# BikeBikeAja_V2.net
KiCad netlist of a schematic drawn in EAGLE
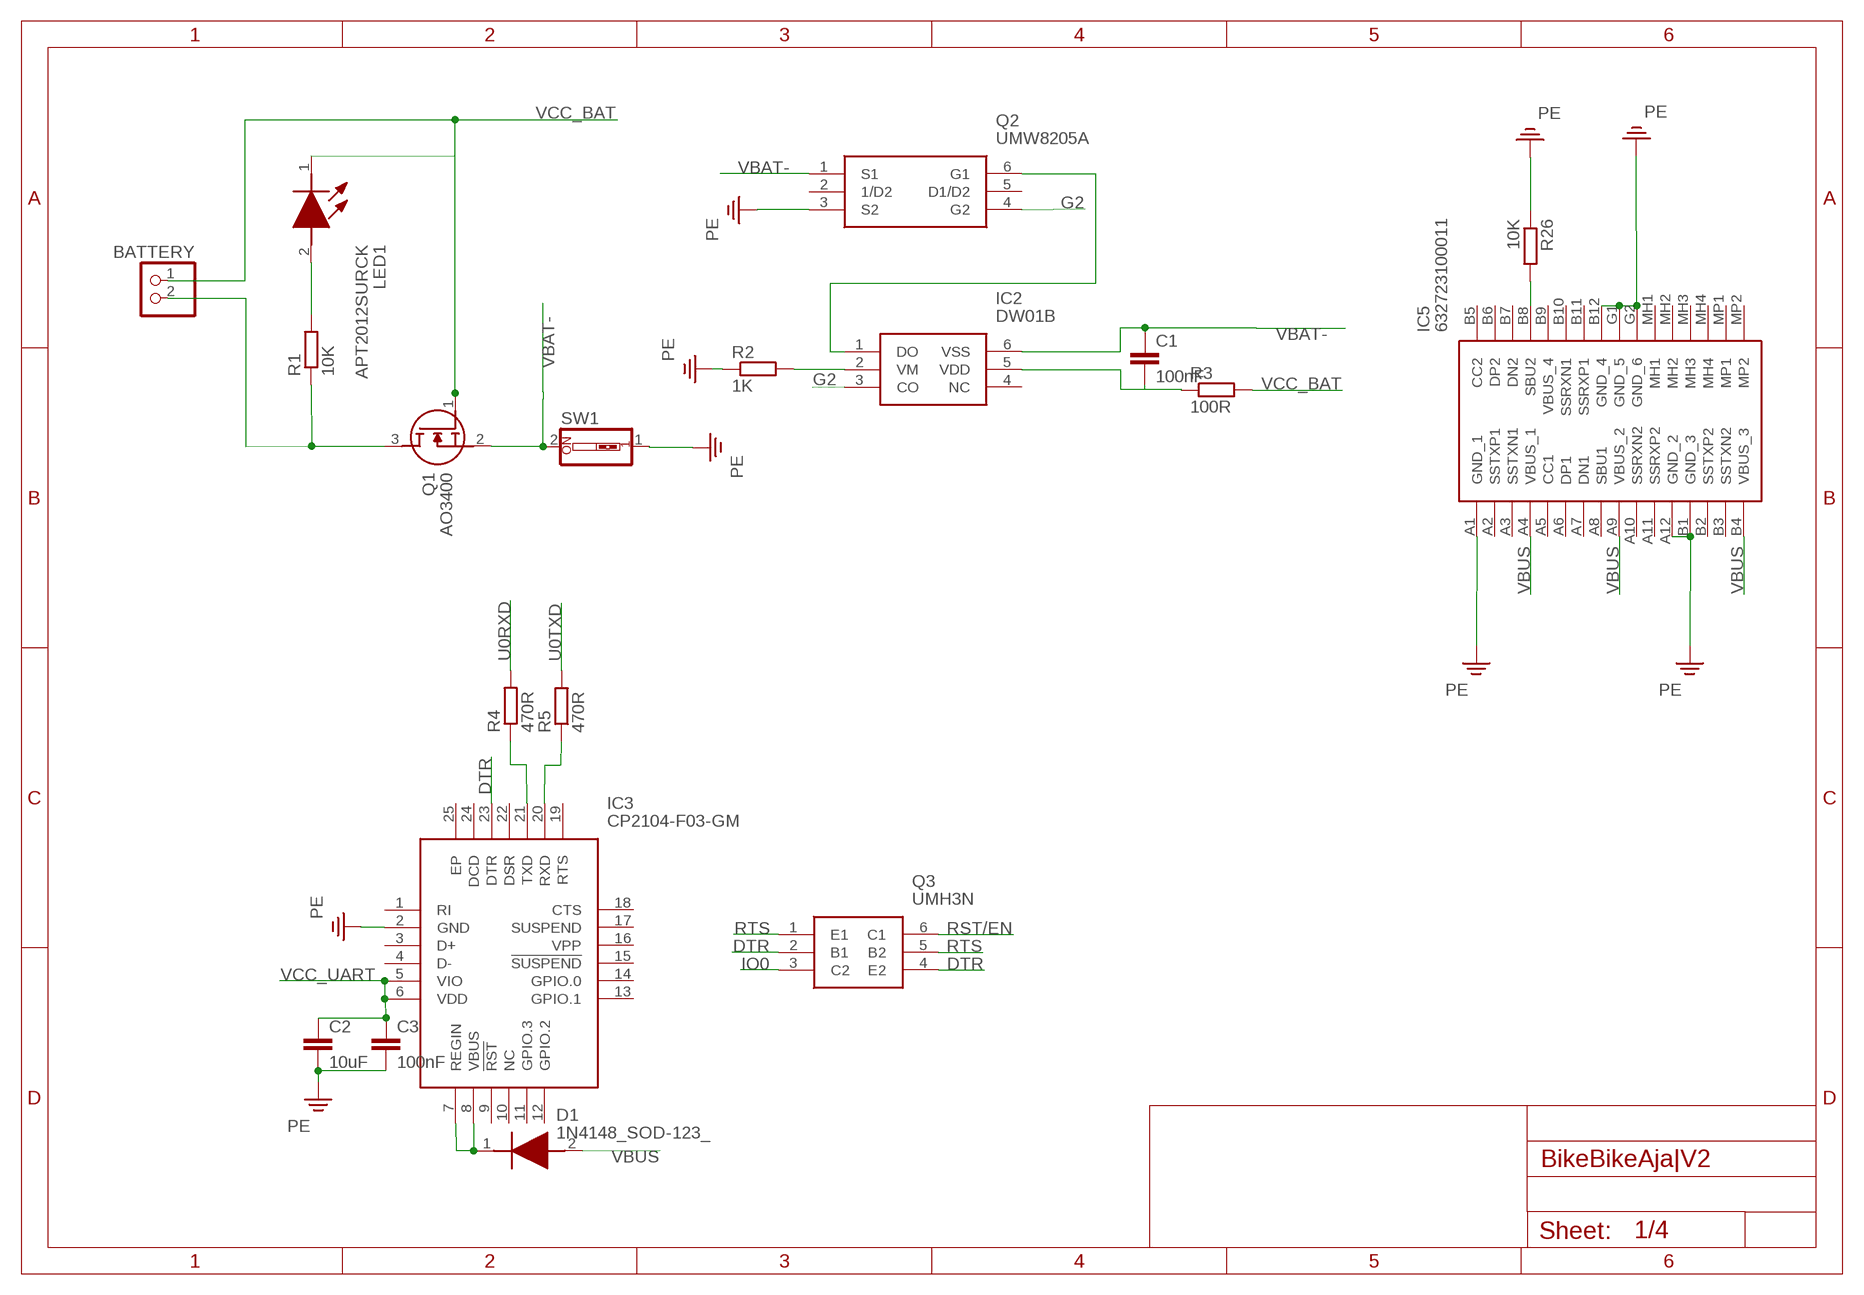
[diagram p0: schematic, sheet 1]
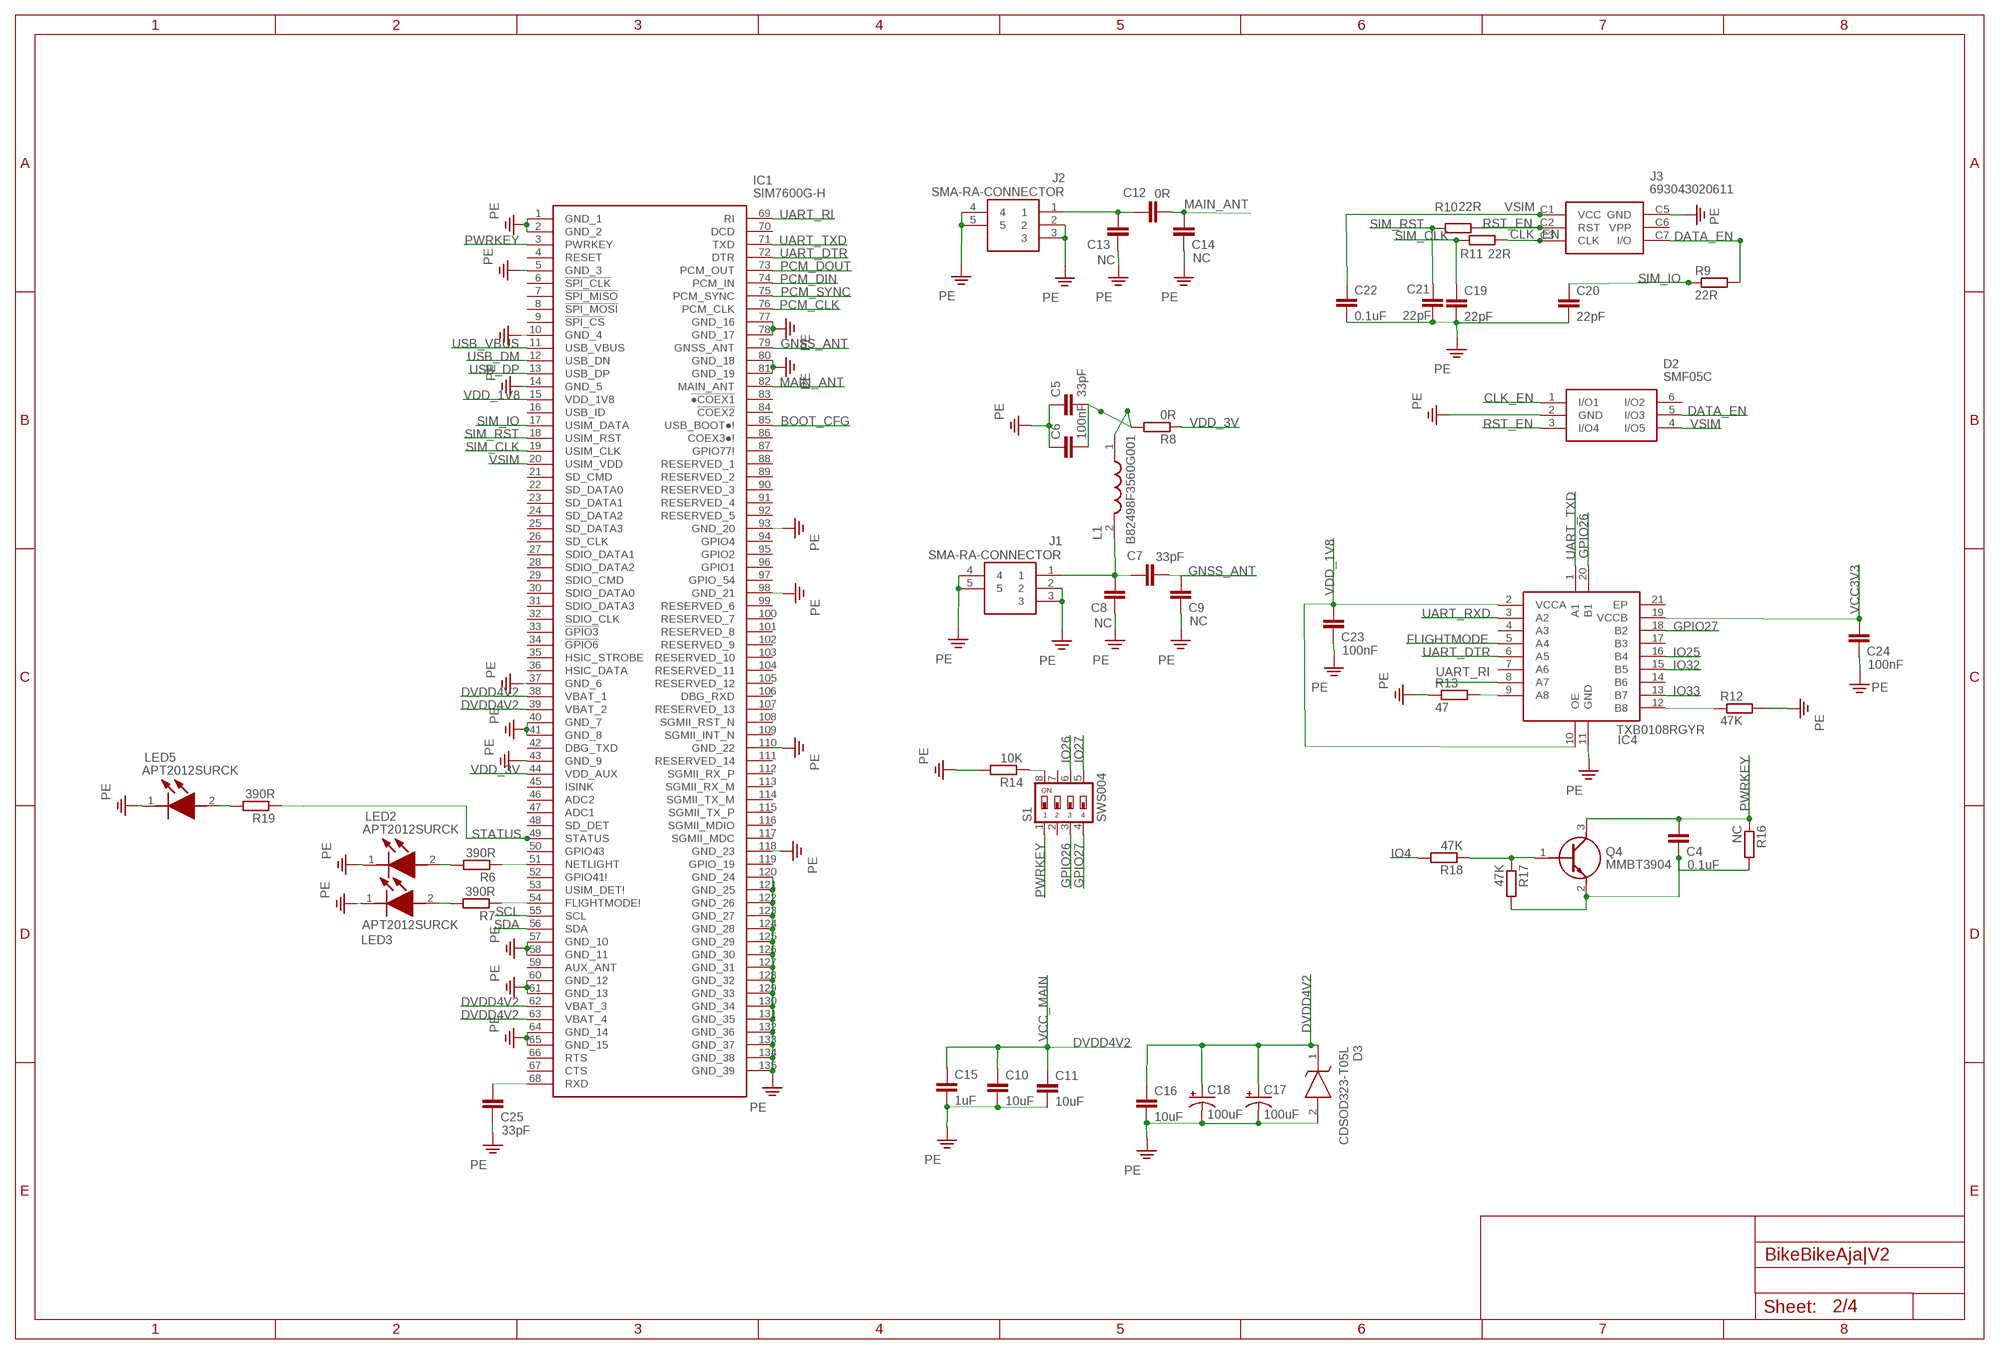
[diagram p1: schematic, sheet 2]
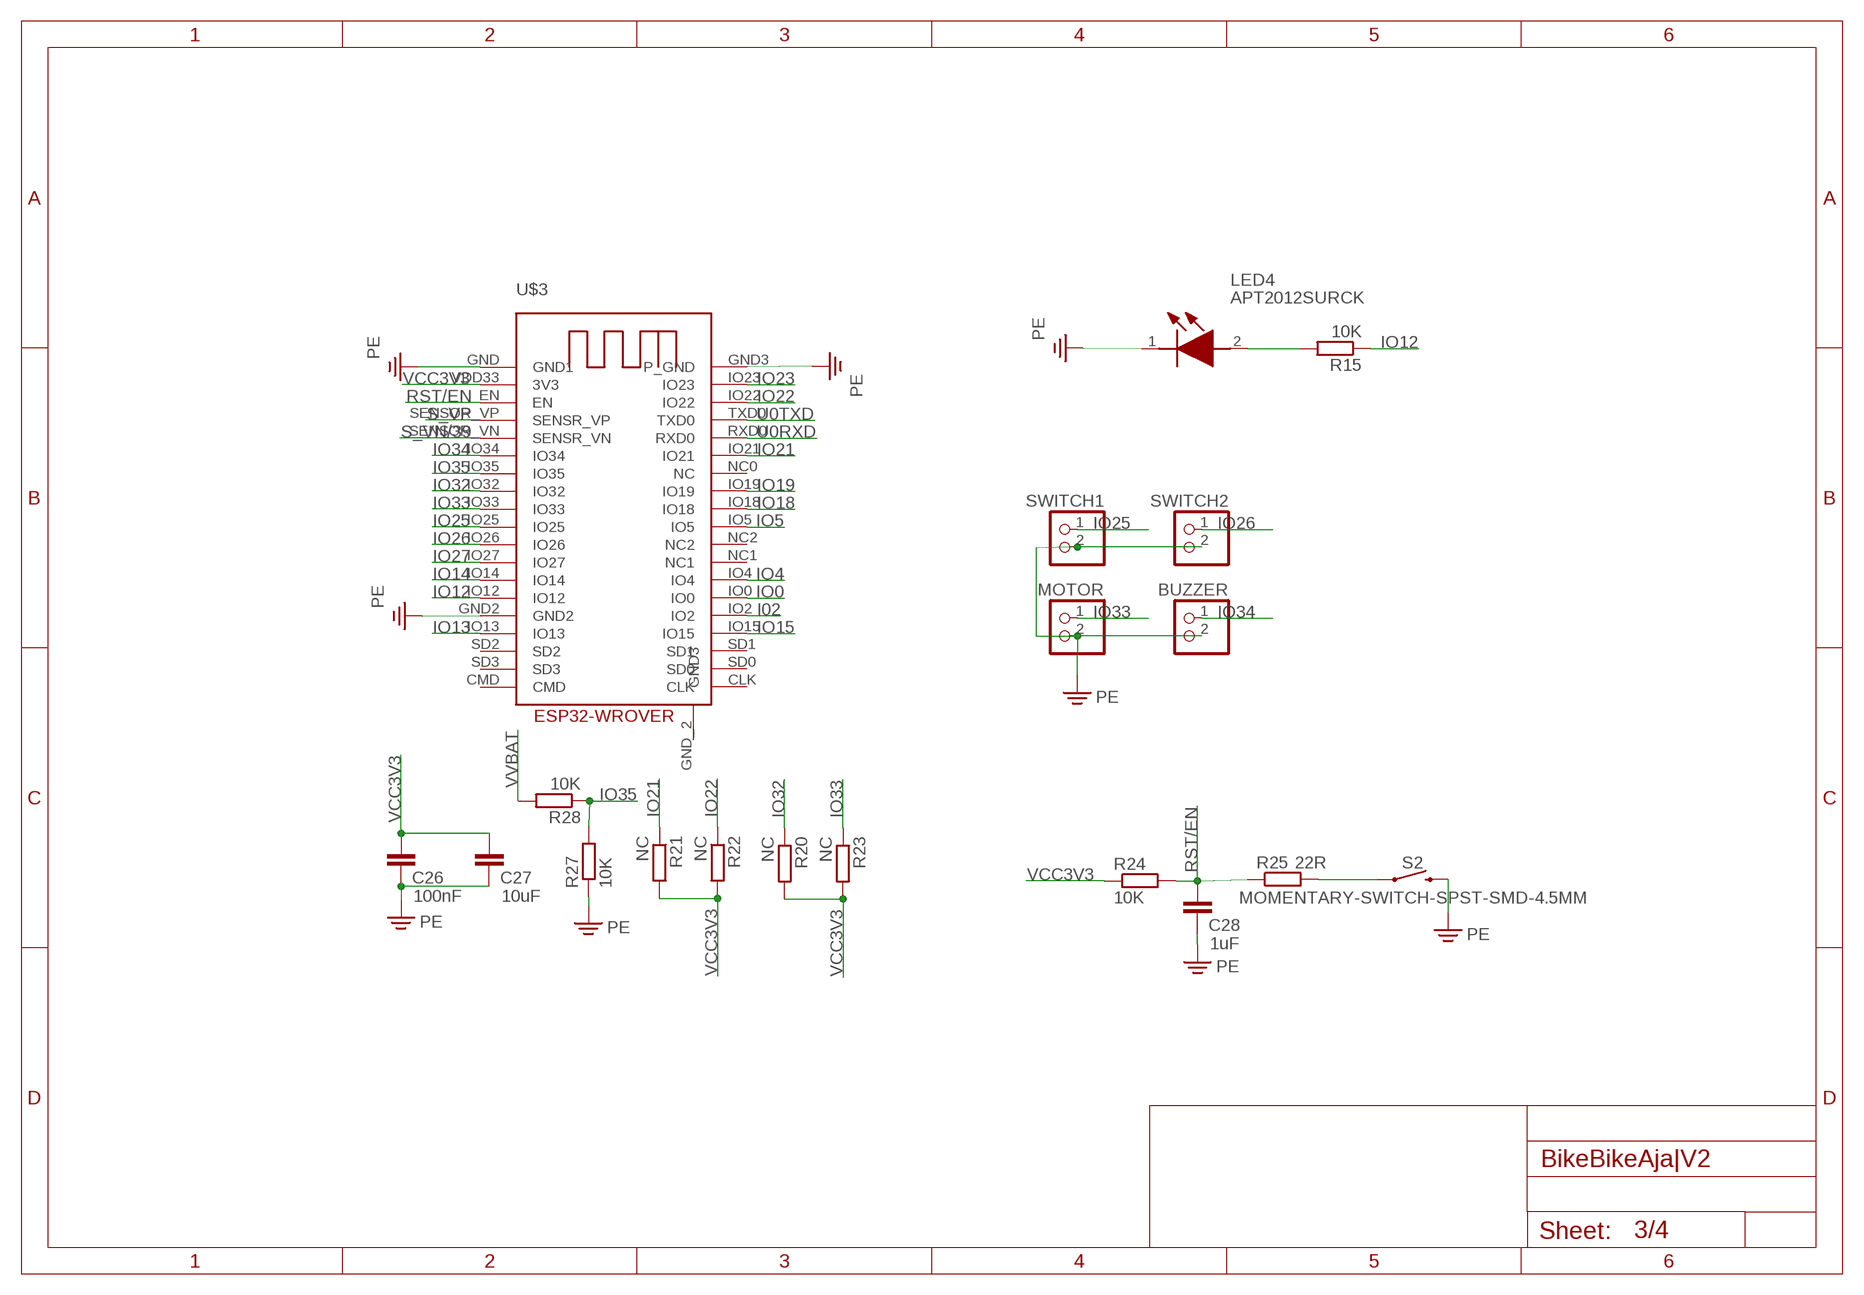
[diagram p2: schematic, sheet 3]
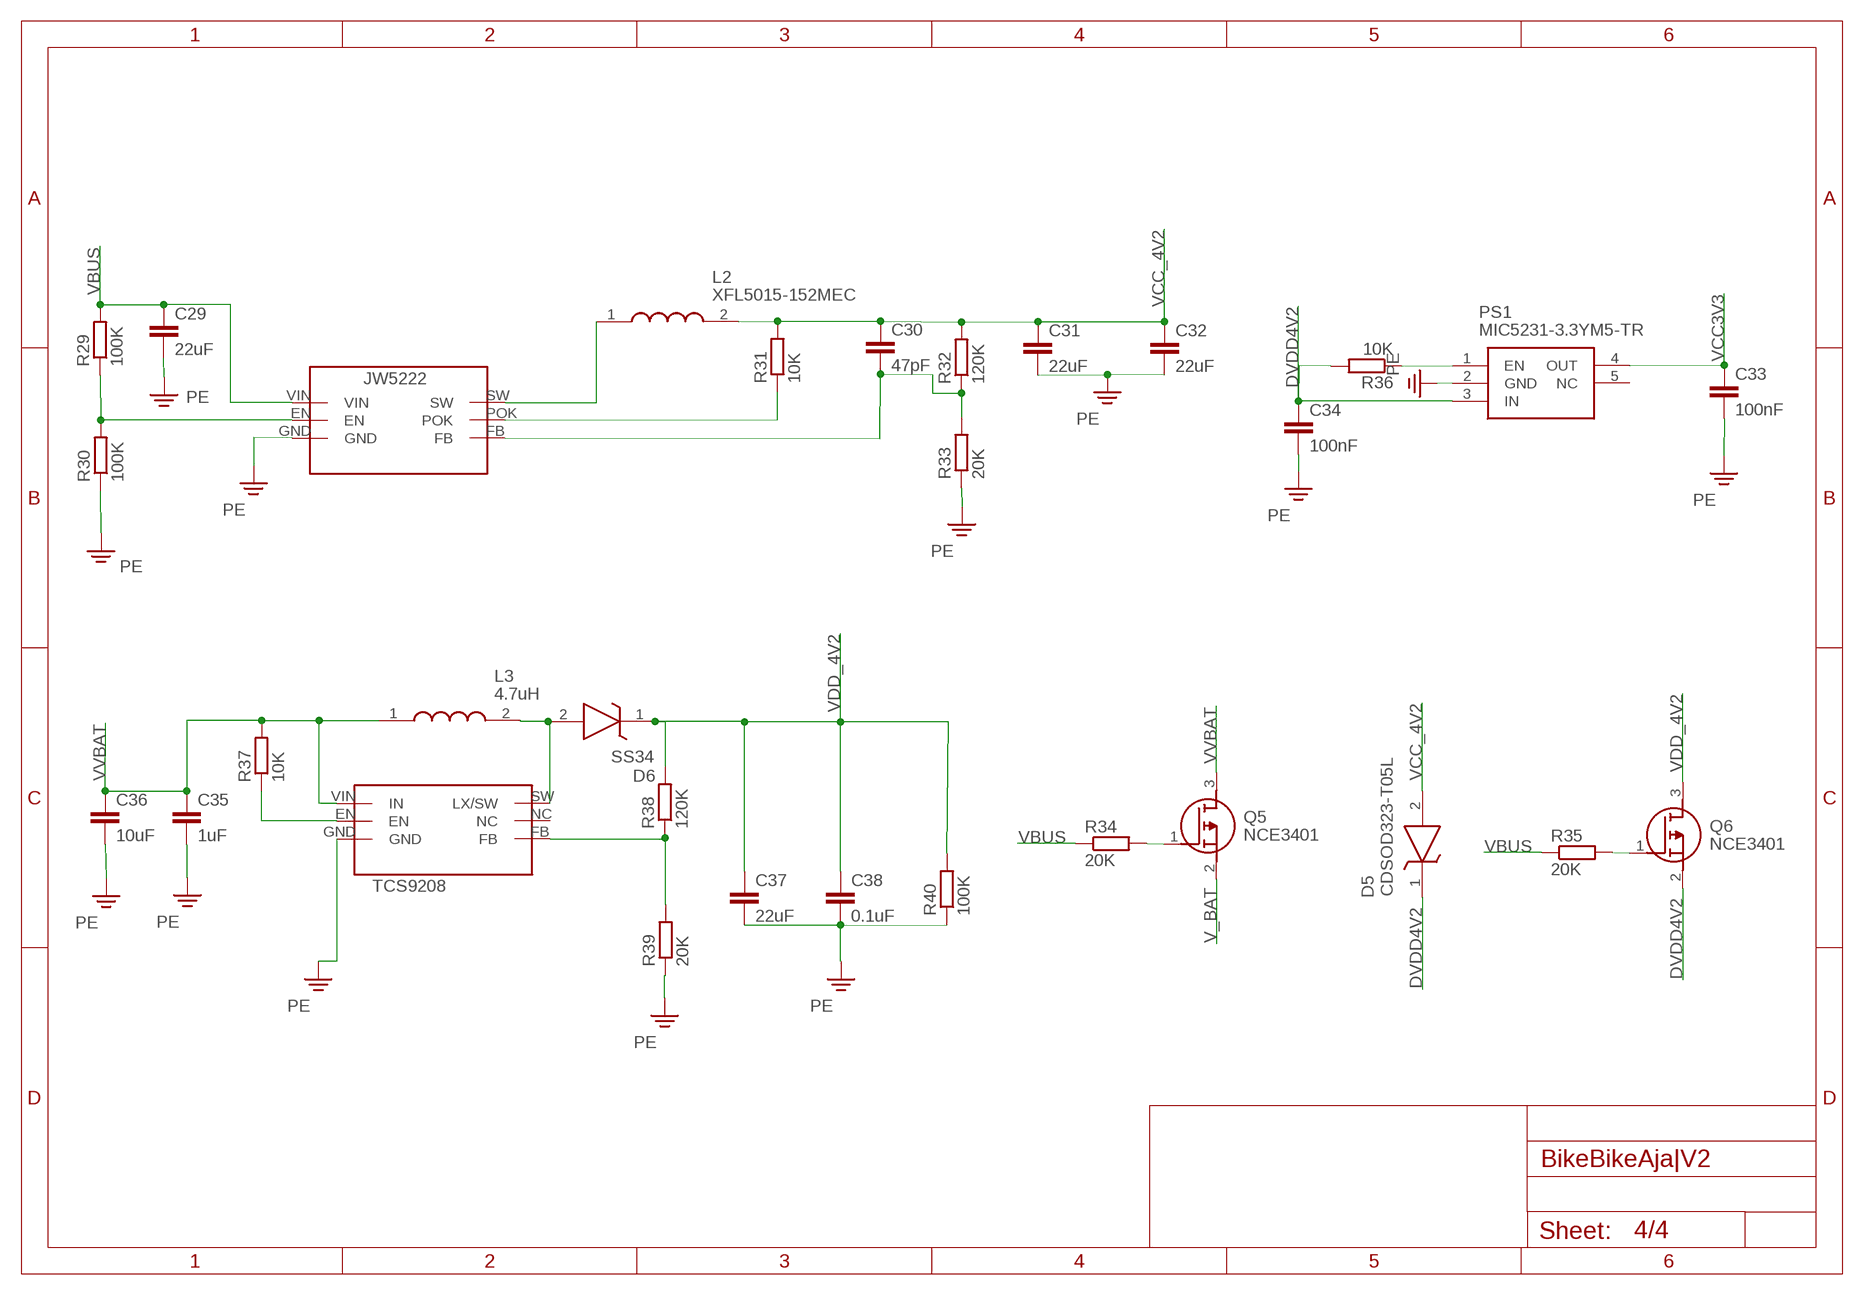
[diagram p3: schematic, sheet 4]

(export (version "E")
  (design (tool "Eeschema 10.0.6"))
  (components
    (comp (ref "BUZZER")
      (value "PINHD-1X2")
      (footprint "eagle-import:1X02")
      (libsource (lib "eagle-import") (part "PINHD-1X2"))
    )
    (comp (ref "C26")
      (value "100nF")
      (footprint "eagle-import:C1206")
      (libsource (lib "eagle-import") (part "C-EUC1206"))
    )
    (comp (ref "C27")
      (value "10uF")
      (footprint "eagle-import:C1206")
      (libsource (lib "eagle-import") (part "C-EUC1206"))
    )
    (comp (ref "C28")
      (value "1uF")
      (footprint "eagle-import:C1206")
      (libsource (lib "eagle-import") (part "C-EUC1206"))
    )
    (comp (ref "LED4")
      (value "APT2012SURCK")
      (footprint "eagle-import:LEDC2012X85N")
      (fields (field (name "MOUSER_PART_NUMBER") "604-APT2012SURCK"))
      (libsource (lib "eagle-import") (part "APT2012SURCK"))
    )
    (comp (ref "MOTOR")
      (value "PINHD-1X2")
      (footprint "eagle-import:1X02")
      (libsource (lib "eagle-import") (part "PINHD-1X2"))
    )
    (comp (ref "R15")
      (value "10K")
      (footprint "eagle-import:R0805")
      (libsource (lib "eagle-import") (part "R-EU_R0805"))
    )
    (comp (ref "R20")
      (value "NC")
      (footprint "eagle-import:R0805")
      (libsource (lib "eagle-import") (part "R-EU_R0805"))
    )
    (comp (ref "R21")
      (value "NC")
      (footprint "eagle-import:R0805")
      (libsource (lib "eagle-import") (part "R-EU_R0805"))
    )
    (comp (ref "R22")
      (value "NC")
      (footprint "eagle-import:R0805")
      (libsource (lib "eagle-import") (part "R-EU_R0805"))
    )
    (comp (ref "R23")
      (value "NC")
      (footprint "eagle-import:R0805")
      (libsource (lib "eagle-import") (part "R-EU_R0805"))
    )
    (comp (ref "R24")
      (value "10K")
      (footprint "eagle-import:R0805")
      (libsource (lib "eagle-import") (part "R-EU_R0805"))
    )
    (comp (ref "R25")
      (value "22R")
      (footprint "eagle-import:R0805")
      (libsource (lib "eagle-import") (part "R-EU_R0805"))
    )
    (comp (ref "R27")
      (value "10K")
      (footprint "eagle-import:R0805")
      (libsource (lib "eagle-import") (part "R-EU_R0805"))
    )
    (comp (ref "R28")
      (value "10K")
      (footprint "eagle-import:R0805")
      (libsource (lib "eagle-import") (part "R-EU_R0805"))
    )
    (comp (ref "S2")
      (value "MOMENTARY-SWITCH-SPST-SMD-4.5MM")
      (footprint "eagle-import:TACTILE_SWITCH_SMD_4.5MM")
      (libsource (lib "eagle-import") (part "MOMENTARY-SWITCH-SPST-SMD-4.5MM"))
    )
    (comp (ref "SWITCH1")
      (value "PINHD-1X2")
      (footprint "eagle-import:1X02")
      (libsource (lib "eagle-import") (part "PINHD-1X2"))
    )
    (comp (ref "SWITCH2")
      (value "PINHD-1X2")
      (footprint "eagle-import:1X02")
      (libsource (lib "eagle-import") (part "PINHD-1X2"))
    )
    (comp (ref "U$3")
      (value "ESP32-WROVER")
      (footprint "eagle-import:ESP32-WROVER")
      (libsource (lib "eagle-import") (part "ESP32-WROVER"))
    )
    (comp (ref "BATTERY")
      (value "PINHD-1X2")
      (footprint "eagle-import:1X02")
      (libsource (lib "eagle-import") (part "PINHD-1X2"))
    )
    (comp (ref "C1")
      (value "100nF")
      (footprint "eagle-import:C1206")
      (libsource (lib "eagle-import") (part "C-EUC1206"))
    )
    (comp (ref "C2")
      (value "10uF")
      (footprint "eagle-import:C1206")
      (libsource (lib "eagle-import") (part "C-EUC1206"))
    )
    (comp (ref "C3")
      (value "100nF")
      (footprint "eagle-import:C1206")
      (libsource (lib "eagle-import") (part "C-EUC1206"))
    )
    (comp (ref "D1")
      (value "1N4148_SOD-123_")
      (footprint "eagle-import:SOD3716X135N")
      (fields (field (name "MANUFACTURER_PART_NUMBER") "1N4148(SOD-123)"))
      (libsource (lib "eagle-import") (part "1N4148_SOD-123_"))
    )
    (comp (ref "IC2")
      (value "DW01B")
      (footprint "eagle-import:SOT95P280X145-6N")
      (libsource (lib "eagle-import") (part "DW01B"))
    )
    (comp (ref "IC3")
      (value "CP2104-F03-GM")
      (footprint "eagle-import:QFN50P400X400X80-25N")
      (fields (field (name "MOUSER_PART_NUMBER") "634-CP2104-F03-GM"))
      (libsource (lib "eagle-import") (part "CP2104-F03-GM"))
    )
    (comp (ref "IC5")
      (value "632723100011")
      (footprint "eagle-import:632723100011")
      (fields (field (name "MOUSER_PART_NUMBER") "710-632723100011"))
      (libsource (lib "eagle-import") (part "632723100011"))
    )
    (comp (ref "LED1")
      (value "APT2012SURCK")
      (footprint "eagle-import:LEDC2012X85N")
      (fields (field (name "MOUSER_PART_NUMBER") "604-APT2012SURCK"))
      (libsource (lib "eagle-import") (part "APT2012SURCK"))
    )
    (comp (ref "Q1")
      (value "AO3400")
      (footprint "eagle-import:SOT95P280X125-3N")
      (libsource (lib "eagle-import") (part "AO3400"))
    )
    (comp (ref "Q2")
      (value "UMW8205A")
      (footprint "eagle-import:SOT95P285X140-6N")
      (libsource (lib "eagle-import") (part "UMW8205A"))
    )
    (comp (ref "Q3")
      (value "UMH3N")
      (footprint "eagle-import:SOT65P230X110-6N")
      (libsource (lib "eagle-import") (part "UMH3N"))
    )
    (comp (ref "R1")
      (value "10K")
      (footprint "eagle-import:R0805")
      (libsource (lib "eagle-import") (part "R-EU_R0805"))
    )
    (comp (ref "R2")
      (value "1K")
      (footprint "eagle-import:R0805")
      (libsource (lib "eagle-import") (part "R-EU_R0805"))
    )
    (comp (ref "R3")
      (value "100R")
      (footprint "eagle-import:R0805")
      (libsource (lib "eagle-import") (part "R-EU_R0805"))
    )
    (comp (ref "R4")
      (value "470R")
      (footprint "eagle-import:R0805")
      (libsource (lib "eagle-import") (part "R-EU_R0805"))
    )
    (comp (ref "R5")
      (value "470R")
      (footprint "eagle-import:R0805")
      (libsource (lib "eagle-import") (part "R-EU_R0805"))
    )
    (comp (ref "R26")
      (value "10K")
      (footprint "eagle-import:R0805")
      (libsource (lib "eagle-import") (part "R-EU_R0805"))
    )
    (comp (ref "SW1")
      (value "SW_DIP-1")
      (footprint "eagle-import:EDG-01")
      (libsource (lib "eagle-import") (part "SW_DIP-1"))
    )
    (comp (ref "C29")
      (value "22uF")
      (footprint "eagle-import:C1206")
      (libsource (lib "eagle-import") (part "C-EUC1206"))
    )
    (comp (ref "C30")
      (value "47pF")
      (footprint "eagle-import:C1206")
      (libsource (lib "eagle-import") (part "C-EUC1206"))
    )
    (comp (ref "C31")
      (value "22uF")
      (footprint "eagle-import:C1206")
      (libsource (lib "eagle-import") (part "C-EUC1206"))
    )
    (comp (ref "C32")
      (value "22uF")
      (footprint "eagle-import:C1206")
      (libsource (lib "eagle-import") (part "C-EUC1206"))
    )
    (comp (ref "C33")
      (value "100nF")
      (footprint "eagle-import:C1206")
      (libsource (lib "eagle-import") (part "C-EUC1206"))
    )
    (comp (ref "C34")
      (value "100nF")
      (footprint "eagle-import:C1206")
      (libsource (lib "eagle-import") (part "C-EUC1206"))
    )
    (comp (ref "C35")
      (value "1uF")
      (footprint "eagle-import:C1206")
      (libsource (lib "eagle-import") (part "C-EUC1206"))
    )
    (comp (ref "C36")
      (value "10uF")
      (footprint "eagle-import:C1206")
      (libsource (lib "eagle-import") (part "C-EUC1206"))
    )
    (comp (ref "C37")
      (value "22uF")
      (footprint "eagle-import:C1206")
      (libsource (lib "eagle-import") (part "C-EUC1206"))
    )
    (comp (ref "C38")
      (value "0.1uF")
      (footprint "eagle-import:C1206")
      (libsource (lib "eagle-import") (part "C-EUC1206"))
    )
    (comp (ref "D5")
      (value "CDSOD323-T05L")
      (footprint "eagle-import:SOD2513X114N")
      (fields (field (name "MOUSER_PART_NUMBER") "652-CDSOD323-T05L"))
      (libsource (lib "eagle-import") (part "CDSOD323-T05L"))
    )
    (comp (ref "D6")
      (value "SS34")
      (footprint "eagle-import:SOD2513X114N")
      (fields
        (field (name "ARROW_PART_NUMBER") "CDSOD323-T05L")
        (field (name "MOUSER_PART_NUMBER") "652-CDSOD323-T05L")
      )
      (libsource (lib "eagle-import") (part "CDSOD323-T05L"))
    )
    (comp (ref "L2")
      (value "XFL5015-152MEC")
      (footprint "eagle-import:XFL5015152MEC")
      (libsource (lib "eagle-import") (part "XFL5015-152MEC"))
    )
    (comp (ref "L3")
      (value "4.7uH")
      (footprint "eagle-import:XFL5015152MEC")
      (fields (field (name "MANUFACTURER_PART_NUMBER") "XFL5015-152MEC"))
      (libsource (lib "eagle-import") (part "XFL5015-152MEC"))
    )
    (comp (ref "PS1")
      (value "MIC5231-3.3YM5-TR")
      (footprint "eagle-import:SOT95P280X145-5N")
      (fields (field (name "MOUSER_PART_NUMBER") "998-MIC5231-3.3YM5TR"))
      (libsource (lib "eagle-import") (part "MIC5231-3.3YM5-TR"))
    )
    (comp (ref "Q5")
      (value "NCE3401")
      (footprint "eagle-import:SOT95P240X115-3N")
      (libsource (lib "eagle-import") (part "NCE3401"))
    )
    (comp (ref "Q6")
      (value "NCE3401")
      (footprint "eagle-import:SOT95P240X115-3N")
      (libsource (lib "eagle-import") (part "NCE3401"))
    )
    (comp (ref "R29")
      (value "100K")
      (footprint "eagle-import:R0805")
      (libsource (lib "eagle-import") (part "R-EU_R0805"))
    )
    (comp (ref "R30")
      (value "100K")
      (footprint "eagle-import:R0805")
      (libsource (lib "eagle-import") (part "R-EU_R0805"))
    )
    (comp (ref "R31")
      (value "10K")
      (footprint "eagle-import:R0805")
      (libsource (lib "eagle-import") (part "R-EU_R0805"))
    )
    (comp (ref "R32")
      (value "120K")
      (footprint "eagle-import:R0805")
      (libsource (lib "eagle-import") (part "R-EU_R0805"))
    )
    (comp (ref "R33")
      (value "20K")
      (footprint "eagle-import:R0805")
      (libsource (lib "eagle-import") (part "R-EU_R0805"))
    )
    (comp (ref "R34")
      (value "20K")
      (footprint "eagle-import:R0805")
      (libsource (lib "eagle-import") (part "R-EU_R0805"))
    )
    (comp (ref "R35")
      (value "20K")
      (footprint "eagle-import:R0805")
      (libsource (lib "eagle-import") (part "R-EU_R0805"))
    )
    (comp (ref "R36")
      (value "10K")
      (footprint "eagle-import:R0805")
      (libsource (lib "eagle-import") (part "R-EU_R0805"))
    )
    (comp (ref "R37")
      (value "10K")
      (footprint "eagle-import:R0805")
      (libsource (lib "eagle-import") (part "R-EU_R0805"))
    )
    (comp (ref "R38")
      (value "120K")
      (footprint "eagle-import:R0805")
      (libsource (lib "eagle-import") (part "R-EU_R0805"))
    )
    (comp (ref "R39")
      (value "20K")
      (footprint "eagle-import:R0805")
      (libsource (lib "eagle-import") (part "R-EU_R0805"))
    )
    (comp (ref "R40")
      (value "100K")
      (footprint "eagle-import:R0805")
      (libsource (lib "eagle-import") (part "R-EU_R0805"))
    )
    (comp (ref "U$1")
      (value "JW5222")
      (footprint "eagle-import:JW5222")
      (libsource (lib "eagle-import") (part "JW5222"))
    )
    (comp (ref "U$4")
      (value "TCS9208")
      (footprint "eagle-import:TCS9208")
      (libsource (lib "eagle-import") (part "TCS9208"))
    )
    (comp (ref "C4")
      (value "0.1uF")
      (footprint "eagle-import:C1206")
      (libsource (lib "eagle-import") (part "C-EUC1206"))
    )
    (comp (ref "C5")
      (value "33pF")
      (footprint "eagle-import:C1206")
      (libsource (lib "eagle-import") (part "C-EUC1206"))
    )
    (comp (ref "C6")
      (value "100nF")
      (footprint "eagle-import:C1206")
      (libsource (lib "eagle-import") (part "C-EUC1206"))
    )
    (comp (ref "C7")
      (value "33pF")
      (footprint "eagle-import:C1206")
      (libsource (lib "eagle-import") (part "C-EUC1206"))
    )
    (comp (ref "C8")
      (value "NC")
      (footprint "eagle-import:C1206")
      (libsource (lib "eagle-import") (part "C-EUC1206"))
    )
    (comp (ref "C9")
      (value "NC")
      (footprint "eagle-import:C1206")
      (libsource (lib "eagle-import") (part "C-EUC1206"))
    )
    (comp (ref "C10")
      (value "10uF")
      (footprint "eagle-import:C1206")
      (libsource (lib "eagle-import") (part "C-EUC1206"))
    )
    (comp (ref "C11")
      (value "10uF")
      (footprint "eagle-import:C1206")
      (libsource (lib "eagle-import") (part "C-EUC1206"))
    )
    (comp (ref "C12")
      (value "0R")
      (footprint "eagle-import:C1206")
      (libsource (lib "eagle-import") (part "C-EUC1206"))
    )
    (comp (ref "C13")
      (value "NC")
      (footprint "eagle-import:C1206")
      (libsource (lib "eagle-import") (part "C-EUC1206"))
    )
    (comp (ref "C14")
      (value "NC")
      (footprint "eagle-import:C1206")
      (libsource (lib "eagle-import") (part "C-EUC1206"))
    )
    (comp (ref "C15")
      (value "1uF")
      (footprint "eagle-import:C1206")
      (libsource (lib "eagle-import") (part "C-EUC1206"))
    )
    (comp (ref "C16")
      (value "10uF")
      (footprint "eagle-import:C1206")
      (libsource (lib "eagle-import") (part "C-EUC1206"))
    )
    (comp (ref "C17")
      (value "100uF")
      (footprint "eagle-import:A_3216-18W")
      (libsource (lib "eagle-import") (part "CPOL-USA/3216-18W"))
    )
    (comp (ref "C18")
      (value "100uF")
      (footprint "eagle-import:A_3216-18W")
      (libsource (lib "eagle-import") (part "CPOL-USA/3216-18W"))
    )
    (comp (ref "C19")
      (value "22pF")
      (footprint "eagle-import:C1206")
      (libsource (lib "eagle-import") (part "C-EUC1206"))
    )
    (comp (ref "C20")
      (value "22pF")
      (footprint "eagle-import:C1206")
      (libsource (lib "eagle-import") (part "C-EUC1206"))
    )
    (comp (ref "C21")
      (value "22pF")
      (footprint "eagle-import:C1206")
      (libsource (lib "eagle-import") (part "C-EUC1206"))
    )
    (comp (ref "C22")
      (value "0.1uF")
      (footprint "eagle-import:C1206")
      (libsource (lib "eagle-import") (part "C-EUC1206"))
    )
    (comp (ref "C23")
      (value "100nF")
      (footprint "eagle-import:C1206")
      (libsource (lib "eagle-import") (part "C-EUC1206"))
    )
    (comp (ref "C24")
      (value "100nF")
      (footprint "eagle-import:C1206")
      (libsource (lib "eagle-import") (part "C-EUC1206"))
    )
    (comp (ref "C25")
      (value "33pF")
      (footprint "eagle-import:C1206")
      (libsource (lib "eagle-import") (part "C-EUC1206"))
    )
    (comp (ref "D2")
      (value "SMF05C")
      (footprint "eagle-import:SOT65P210X110-6N")
      (libsource (lib "eagle-import") (part "SMF05C"))
    )
    (comp (ref "D3")
      (value "CDSOD323-T05L")
      (footprint "eagle-import:SOD2513X114N")
      (fields (field (name "MOUSER_PART_NUMBER") "652-CDSOD323-T05L"))
      (libsource (lib "eagle-import") (part "CDSOD323-T05L"))
    )
    (comp (ref "IC1")
      (value "SIM7600G-H")
      (footprint "eagle-import:SIM7600GH")
      (libsource (lib "eagle-import") (part "SIM7600G-H"))
    )
    (comp (ref "IC4")
      (value "TXB0108RGYR")
      (footprint "eagle-import:SN74LVC541ARGYR")
      (fields (field (name "MOUSER_PART_NUMBER") "595-TXB0108RGYR"))
      (libsource (lib "eagle-import") (part "TXB0108RGYR"))
    )
    (comp (ref "J1")
      (value "SMA-RA-CONNECTOR")
      (footprint "eagle-import:SMARACONNECTOR")
      (libsource (lib "eagle-import") (part "SMA-RA-CONNECTOR"))
    )
    (comp (ref "J2")
      (value "SMA-RA-CONNECTOR")
      (footprint "eagle-import:SMARACONNECTOR")
      (libsource (lib "eagle-import") (part "SMA-RA-CONNECTOR"))
    )
    (comp (ref "J3")
      (value "693043020611")
      (footprint "eagle-import:693043020611")
      (fields (field (name "MOUSER_PART_NUMBER") "710-693043020611"))
      (libsource (lib "eagle-import") (part "693043020611"))
    )
    (comp (ref "L1")
      (value "B82498F3560G001")
      (footprint "eagle-import:B82498F")
      (libsource (lib "eagle-import") (part "B82498F3560G001"))
    )
    (comp (ref "LED2")
      (value "APT2012SURCK")
      (footprint "eagle-import:LEDC2012X85N")
      (fields (field (name "MOUSER_PART_NUMBER") "604-APT2012SURCK"))
      (libsource (lib "eagle-import") (part "APT2012SURCK"))
    )
    (comp (ref "LED3")
      (value "APT2012SURCK")
      (footprint "eagle-import:LEDC2012X85N")
      (fields (field (name "MOUSER_PART_NUMBER") "604-APT2012SURCK"))
      (libsource (lib "eagle-import") (part "APT2012SURCK"))
    )
    (comp (ref "LED5")
      (value "APT2012SURCK")
      (footprint "eagle-import:LEDC2012X85N")
      (fields (field (name "MOUSER_PART_NUMBER") "604-APT2012SURCK"))
      (libsource (lib "eagle-import") (part "APT2012SURCK"))
    )
    (comp (ref "Q4")
      (value "MMBT3904")
      (footprint "eagle-import:SOT95P240X120-3N")
      (fields (field (name "MOUSER_PART_NUMBER") "512-MMBT3904"))
      (libsource (lib "eagle-import") (part "MMBT3904"))
    )
    (comp (ref "R6")
      (value "390R")
      (footprint "eagle-import:R0805")
      (libsource (lib "eagle-import") (part "R-EU_R0805"))
    )
    (comp (ref "R7")
      (value "390R")
      (footprint "eagle-import:R0805")
      (libsource (lib "eagle-import") (part "R-EU_R0805"))
    )
    (comp (ref "R8")
      (value "0R")
      (footprint "eagle-import:R0805")
      (libsource (lib "eagle-import") (part "R-EU_R0805"))
    )
    (comp (ref "R9")
      (value "22R")
      (footprint "eagle-import:R0805")
      (libsource (lib "eagle-import") (part "R-EU_R0805"))
    )
    (comp (ref "R10")
      (value "22R")
      (footprint "eagle-import:R0805")
      (libsource (lib "eagle-import") (part "R-EU_R0805"))
    )
    (comp (ref "R11")
      (value "22R")
      (footprint "eagle-import:R0805")
      (libsource (lib "eagle-import") (part "R-EU_R0805"))
    )
    (comp (ref "R12")
      (value "47K")
      (footprint "eagle-import:R0805")
      (libsource (lib "eagle-import") (part "R-EU_R0805"))
    )
    (comp (ref "R13")
      (value "47")
      (footprint "eagle-import:R0805")
      (libsource (lib "eagle-import") (part "R-EU_R0805"))
    )
    (comp (ref "R14")
      (value "10K")
      (footprint "eagle-import:R0805")
      (libsource (lib "eagle-import") (part "R-EU_R0805"))
    )
    (comp (ref "R16")
      (value "NC")
      (footprint "eagle-import:R0805")
      (libsource (lib "eagle-import") (part "R-EU_R0805"))
    )
    (comp (ref "R17")
      (value "47K")
      (footprint "eagle-import:R0805")
      (libsource (lib "eagle-import") (part "R-EU_R0805"))
    )
    (comp (ref "R18")
      (value "47K")
      (footprint "eagle-import:R0805")
      (libsource (lib "eagle-import") (part "R-EU_R0805"))
    )
    (comp (ref "R19")
      (value "390R")
      (footprint "eagle-import:R0805")
      (libsource (lib "eagle-import") (part "R-EU_R0805"))
    )
    (comp (ref "S1")
      (value "SWS004")
      (footprint "eagle-import:SMS-004")
      (libsource (lib "eagle-import") (part "SWS004"))
    )
  )
  (nets
    (net (code "1") (name "BOOT_CFG") (class "Default")
      (node (ref "IC1") (pin "85") (pinfunction "USB_BOOT●~{}_85") (pintype "bidirectional"))
    )
    (net (code "2") (name "CLK_EN") (class "Default")
      (node (ref "D2") (pin "1") (pinfunction "I/O1_1") (pintype "bidirectional"))
      (node (ref "J3") (pin "C3") (pinfunction "CLK_C3") (pintype "bidirectional"))
      (node (ref "R11") (pin "1") (pinfunction "1_1") (pintype "passive"))
    )
    (net (code "3") (name "DATA_EN") (class "Default")
      (node (ref "D2") (pin "5") (pinfunction "I/O3_5") (pintype "bidirectional"))
      (node (ref "J3") (pin "C7") (pinfunction "I/O_C7") (pintype "bidirectional"))
    )
    (net (code "4") (name "DTR") (class "Default")
      (node (ref "IC3") (pin "23") (pinfunction "DTR_23") (pintype "bidirectional"))
      (node (ref "Q3") (pin "2") (pinfunction "B1_2") (pintype "bidirectional"))
      (node (ref "Q3") (pin "4") (pinfunction "E2_4") (pintype "bidirectional"))
    )
    (net (code "5") (name "DVDD4V2") (class "Default")
      (node (ref "C34") (pin "1") (pinfunction "1_1") (pintype "passive"))
      (node (ref "D5") (pin "1") (pinfunction "K_1") (pintype "bidirectional"))
      (node (ref "IC1") (pin "38") (pinfunction "VBAT_1_38") (pintype "bidirectional"))
      (node (ref "IC1") (pin "39") (pinfunction "VBAT_2_39") (pintype "bidirectional"))
      (node (ref "IC1") (pin "62") (pinfunction "VBAT_3_62") (pintype "bidirectional"))
      (node (ref "IC1") (pin "63") (pinfunction "VBAT_4_63") (pintype "bidirectional"))
      (node (ref "PS1") (pin "3") (pinfunction "IN_3") (pintype "bidirectional"))
      (node (ref "Q6") (pin "2") (pinfunction "S_2") (pintype "bidirectional"))
      (node (ref "R36") (pin "2") (pinfunction "2_2") (pintype "passive"))
    )
    (net (code "6") (name "FLIGHTMODE") (class "Default")
      (node (ref "IC4") (pin "5") (pinfunction "A4_5") (pintype "bidirectional"))
    )
    (net (code "7") (name "G2") (class "Default")
      (node (ref "IC2") (pin "3") (pinfunction "CO_3") (pintype "bidirectional"))
      (node (ref "Q2") (pin "4") (pinfunction "G2_4") (pintype "bidirectional"))
    )
    (net (code "8") (name "GNSS_ANT") (class "Default")
      (node (ref "IC1") (pin "79") (pinfunction "GNSS_ANT_79") (pintype "bidirectional"))
    )
    (net (code "9") (name "GPIO26") (class "Default")
      (node (ref "IC4") (pin "20") (pinfunction "B1_20") (pintype "bidirectional"))
      (node (ref "S1") (pin "3") (pinfunction "3_3") (pintype "passive"))
    )
    (net (code "10") (name "GPIO27") (class "Default")
      (node (ref "IC4") (pin "18") (pinfunction "B2_18") (pintype "bidirectional"))
      (node (ref "S1") (pin "4") (pinfunction "4_4") (pintype "passive"))
    )
    (net (code "11") (name "I02") (class "Default")
      (node (ref "U$3") (pin "IO2") (pinfunction "IO2_IO2") (pintype "bidirectional"))
    )
    (net (code "12") (name "IO0") (class "Default")
      (node (ref "Q3") (pin "3") (pinfunction "C2_3") (pintype "bidirectional"))
      (node (ref "U$3") (pin "IO0") (pinfunction "IO0_IO0") (pintype "bidirectional"))
    )
    (net (code "13") (name "IO4") (class "Default")
      (node (ref "R18") (pin "2") (pinfunction "2_2") (pintype "passive"))
      (node (ref "U$3") (pin "IO4") (pinfunction "IO4_IO4") (pintype "bidirectional"))
    )
    (net (code "14") (name "IO5") (class "Default")
      (node (ref "U$3") (pin "IO5") (pinfunction "IO5_IO5") (pintype "bidirectional"))
    )
    (net (code "15") (name "IO12") (class "Default")
      (node (ref "R15") (pin "1") (pinfunction "1_1") (pintype "passive"))
      (node (ref "U$3") (pin "IO12") (pinfunction "IO12_IO12") (pintype "bidirectional"))
    )
    (net (code "16") (name "IO13") (class "Default")
      (node (ref "U$3") (pin "IO13") (pinfunction "IO13_IO13") (pintype "bidirectional"))
    )
    (net (code "17") (name "IO14") (class "Default")
      (node (ref "U$3") (pin "IO14") (pinfunction "IO14_IO14") (pintype "bidirectional"))
    )
    (net (code "18") (name "IO15") (class "Default")
      (node (ref "U$3") (pin "IO15") (pinfunction "IO15_IO15") (pintype "bidirectional"))
    )
    (net (code "19") (name "IO18") (class "Default")
      (node (ref "U$3") (pin "IO18") (pinfunction "IO18_IO18") (pintype "bidirectional"))
    )
    (net (code "20") (name "IO19") (class "Default")
      (node (ref "U$3") (pin "IO19") (pinfunction "IO19_IO19") (pintype "bidirectional"))
    )
    (net (code "21") (name "IO21") (class "Default")
      (node (ref "R21") (pin "1") (pinfunction "1_1") (pintype "passive"))
      (node (ref "U$3") (pin "IO21") (pinfunction "IO21_IO21") (pintype "bidirectional"))
    )
    (net (code "22") (name "IO22") (class "Default")
      (node (ref "R22") (pin "1") (pinfunction "1_1") (pintype "passive"))
      (node (ref "U$3") (pin "IO22") (pinfunction "IO22_IO22") (pintype "bidirectional"))
    )
    (net (code "23") (name "IO23") (class "Default")
      (node (ref "U$3") (pin "IO23") (pinfunction "IO23_IO23") (pintype "bidirectional"))
    )
    (net (code "24") (name "IO25") (class "Default")
      (node (ref "IC4") (pin "16") (pinfunction "B4_16") (pintype "bidirectional"))
      (node (ref "SWITCH1") (pin "1") (pinfunction "1_1") (pintype "passive"))
      (node (ref "U$3") (pin "IO25") (pinfunction "IO25_IO25") (pintype "bidirectional"))
    )
    (net (code "25") (name "IO26") (class "Default")
      (node (ref "S1") (pin "6") (pinfunction "6_6") (pintype "passive"))
      (node (ref "SWITCH2") (pin "1") (pinfunction "1_1") (pintype "passive"))
      (node (ref "U$3") (pin "IO26") (pinfunction "IO26_IO26") (pintype "bidirectional"))
    )
    (net (code "26") (name "IO27") (class "Default")
      (node (ref "S1") (pin "5") (pinfunction "5_5") (pintype "passive"))
      (node (ref "U$3") (pin "IO27") (pinfunction "IO27_IO27") (pintype "bidirectional"))
    )
    (net (code "27") (name "IO32") (class "Default")
      (node (ref "IC4") (pin "15") (pinfunction "B5_15") (pintype "bidirectional"))
      (node (ref "R20") (pin "1") (pinfunction "1_1") (pintype "passive"))
      (node (ref "U$3") (pin "IO32") (pinfunction "IO32_IO32") (pintype "bidirectional"))
    )
    (net (code "28") (name "IO33") (class "Default")
      (node (ref "IC4") (pin "13") (pinfunction "B7_13") (pintype "bidirectional"))
      (node (ref "MOTOR") (pin "1") (pinfunction "1_1") (pintype "passive"))
      (node (ref "R23") (pin "1") (pinfunction "1_1") (pintype "passive"))
      (node (ref "U$3") (pin "IO33") (pinfunction "IO33_IO33") (pintype "bidirectional"))
    )
    (net (code "29") (name "IO34") (class "Default")
      (node (ref "BUZZER") (pin "1") (pinfunction "1_1") (pintype "passive"))
      (node (ref "U$3") (pin "IO34") (pinfunction "IO34_IO34") (pintype "bidirectional"))
    )
    (net (code "30") (name "IO35") (class "Default")
      (node (ref "R27") (pin "2") (pinfunction "2_2") (pintype "passive"))
      (node (ref "R28") (pin "1") (pinfunction "1_1") (pintype "passive"))
      (node (ref "U$3") (pin "IO35") (pinfunction "IO35_IO35") (pintype "bidirectional"))
    )
    (net (code "31") (name "MAIN_ANT") (class "Default")
      (node (ref "C12") (pin "2") (pinfunction "2_2") (pintype "passive"))
      (node (ref "C14") (pin "2") (pinfunction "2_2") (pintype "passive"))
      (node (ref "IC1") (pin "82") (pinfunction "MAIN_ANT_82") (pintype "bidirectional"))
    )
    (net (code "32") (name "Net-(C5-Pad1)") (class "Default")
      (node (ref "C5") (pin "1") (pinfunction "1_1") (pintype "passive"))
      (node (ref "C6") (pin "1") (pinfunction "1_1") (pintype "passive"))
    )
    (net (code "33") (name "Net-(C5-Pad2)") (class "Default")
      (node (ref "C5") (pin "2") (pinfunction "2_2") (pintype "passive"))
      (node (ref "C6") (pin "2") (pinfunction "2_2") (pintype "passive"))
      (node (ref "L1") (pin "1") (pinfunction "1_1") (pintype "bidirectional"))
      (node (ref "R8") (pin "2") (pinfunction "2_2") (pintype "passive"))
    )
    (net (code "34") (name "Net-(C7-Pad1)") (class "Default")
      (node (ref "C7") (pin "1") (pinfunction "1_1") (pintype "passive"))
      (node (ref "C8") (pin "2") (pinfunction "2_2") (pintype "passive"))
      (node (ref "J1") (pin "1") (pinfunction "1_1") (pintype "bidirectional"))
      (node (ref "L1") (pin "2") (pinfunction "2_2") (pintype "bidirectional"))
    )
    (net (code "35") (name "Net-(C7-Pad2)") (class "Default")
      (node (ref "C7") (pin "2") (pinfunction "2_2") (pintype "passive"))
      (node (ref "C9") (pin "2") (pinfunction "2_2") (pintype "passive"))
    )
    (net (code "36") (name "Net-(C10-Pad1)") (class "Default")
      (node (ref "C10") (pin "1") (pinfunction "1_1") (pintype "passive"))
      (node (ref "C11") (pin "1") (pinfunction "1_1") (pintype "passive"))
      (node (ref "C15") (pin "1") (pinfunction "1_1") (pintype "passive"))
    )
    (net (code "37") (name "Net-(C12-Pad1)") (class "Default")
      (node (ref "C12") (pin "1") (pinfunction "1_1") (pintype "passive"))
      (node (ref "C13") (pin "2") (pinfunction "2_2") (pintype "passive"))
      (node (ref "J2") (pin "1") (pinfunction "1_1") (pintype "bidirectional"))
    )
    (net (code "38") (name "Net-(C30-Pad2)") (class "Default")
      (node (ref "C30") (pin "2") (pinfunction "2_2") (pintype "passive"))
      (node (ref "R32") (pin "1") (pinfunction "1_1") (pintype "passive"))
      (node (ref "R33") (pin "2") (pinfunction "2_2") (pintype "passive"))
      (node (ref "U$1") (pin "FB") (pinfunction "FB_FB") (pintype "bidirectional"))
    )
    (net (code "39") (name "Net-(D1-K)") (class "Default")
      (node (ref "D1") (pin "1") (pinfunction "K_1") (pintype "bidirectional"))
      (node (ref "IC3") (pin "7") (pinfunction "REGIN_7") (pintype "bidirectional"))
      (node (ref "IC3") (pin "8") (pinfunction "VBUS_8") (pintype "bidirectional"))
    )
    (net (code "40") (name "Net-(D3-K)") (class "Default")
      (node (ref "C16") (pin "1") (pinfunction "1_1") (pintype "passive"))
      (node (ref "C17") (pin "+") (pinfunction "+_+") (pintype "passive"))
      (node (ref "C18") (pin "+") (pinfunction "+_+") (pintype "passive"))
      (node (ref "D3") (pin "1") (pinfunction "K_1") (pintype "bidirectional"))
    )
    (net (code "41") (name "Net-(D6-A)") (class "Default")
      (node (ref "D6") (pin "2") (pinfunction "A_2") (pintype "bidirectional"))
      (node (ref "L3") (pin "2") (pinfunction "2_2") (pintype "bidirectional"))
      (node (ref "U$4") (pin "SW") (pinfunction "LX/SW_SW") (pintype "bidirectional"))
    )
    (net (code "42") (name "Net-(IC1-FLIGHTMODE~{})") (class "Default")
      (node (ref "IC1") (pin "54") (pinfunction "FLIGHTMODE~{}_54") (pintype "bidirectional"))
      (node (ref "R7") (pin "1") (pinfunction "1_1") (pintype "passive"))
    )
    (net (code "43") (name "Net-(IC1-NETLIGHT)") (class "Default")
      (node (ref "IC1") (pin "51") (pinfunction "NETLIGHT_51") (pintype "bidirectional"))
      (node (ref "R6") (pin "1") (pinfunction "1_1") (pintype "passive"))
    )
    (net (code "44") (name "Net-(IC1-RXD)") (class "Default")
      (node (ref "C25") (pin "2") (pinfunction "2_2") (pintype "passive"))
      (node (ref "IC1") (pin "68") (pinfunction "RXD_68") (pintype "bidirectional"))
    )
    (net (code "45") (name "Net-(IC2-DO)") (class "Default")
      (node (ref "IC2") (pin "1") (pinfunction "DO_1") (pintype "bidirectional"))
      (node (ref "Q2") (pin "6") (pinfunction "G1_6") (pintype "bidirectional"))
    )
    (net (code "46") (name "Net-(IC2-VDD)") (class "Default")
      (node (ref "C1") (pin "2") (pinfunction "2_2") (pintype "passive"))
      (node (ref "IC2") (pin "5") (pinfunction "VDD_5") (pintype "bidirectional"))
      (node (ref "R3") (pin "1") (pinfunction "1_1") (pintype "passive"))
    )
    (net (code "47") (name "Net-(IC2-VM)") (class "Default")
      (node (ref "IC2") (pin "2") (pinfunction "VM_2") (pintype "bidirectional"))
      (node (ref "R2") (pin "2") (pinfunction "2_2") (pintype "passive"))
    )
    (net (code "48") (name "Net-(IC2-VSS)") (class "Default")
      (node (ref "C1") (pin "1") (pinfunction "1_1") (pintype "passive"))
      (node (ref "IC2") (pin "6") (pinfunction "VSS_6") (pintype "bidirectional"))
    )
    (net (code "49") (name "Net-(IC3-RXD)") (class "Default")
      (node (ref "IC3") (pin "20") (pinfunction "RXD_20") (pintype "bidirectional"))
      (node (ref "R5") (pin "1") (pinfunction "1_1") (pintype "passive"))
    )
    (net (code "50") (name "Net-(IC3-TXD)") (class "Default")
      (node (ref "IC3") (pin "21") (pinfunction "TXD_21") (pintype "bidirectional"))
      (node (ref "R4") (pin "1") (pinfunction "1_1") (pintype "passive"))
    )
    (net (code "51") (name "Net-(IC4-A8)") (class "Default")
      (node (ref "IC4") (pin "9") (pinfunction "A8_9") (pintype "bidirectional"))
      (node (ref "R13") (pin "2") (pinfunction "2_2") (pintype "passive"))
    )
    (net (code "52") (name "Net-(IC4-B8)") (class "Default")
      (node (ref "IC4") (pin "12") (pinfunction "B8_12") (pintype "bidirectional"))
      (node (ref "R12") (pin "1") (pinfunction "1_1") (pintype "passive"))
    )
    (net (code "53") (name "Net-(IC5-SBU2)") (class "Default")
      (node (ref "IC5") (pin "B8") (pinfunction "SBU2_B8") (pintype "bidirectional"))
      (node (ref "R26") (pin "2") (pinfunction "2_2") (pintype "passive"))
    )
    (net (code "54") (name "Net-(L2-Pad1)") (class "Default")
      (node (ref "L2") (pin "1") (pinfunction "1_1") (pintype "bidirectional"))
      (node (ref "U$1") (pin "SW") (pinfunction "SW_SW") (pintype "bidirectional"))
    )
    (net (code "55") (name "Net-(LED1-A)") (class "Default")
      (node (ref "LED1") (pin "2") (pinfunction "A_2") (pintype "bidirectional"))
      (node (ref "R1") (pin "2") (pinfunction "2_2") (pintype "passive"))
    )
    (net (code "56") (name "Net-(LED1-K)") (class "Default")
      (node (ref "BATTERY") (pin "1") (pinfunction "1_1") (pintype "passive"))
      (node (ref "LED1") (pin "1") (pinfunction "K_1") (pintype "bidirectional"))
      (node (ref "Q1") (pin "1") (pinfunction "G_1") (pintype "bidirectional"))
    )
    (net (code "57") (name "Net-(LED2-A)") (class "Default")
      (node (ref "LED2") (pin "2") (pinfunction "A_2") (pintype "bidirectional"))
      (node (ref "R6") (pin "2") (pinfunction "2_2") (pintype "passive"))
    )
    (net (code "58") (name "Net-(LED3-A)") (class "Default")
      (node (ref "LED3") (pin "2") (pinfunction "A_2") (pintype "bidirectional"))
      (node (ref "R7") (pin "2") (pinfunction "2_2") (pintype "passive"))
    )
    (net (code "59") (name "Net-(LED4-A)") (class "Default")
      (node (ref "LED4") (pin "2") (pinfunction "A_2") (pintype "bidirectional"))
      (node (ref "R15") (pin "2") (pinfunction "2_2") (pintype "passive"))
    )
    (net (code "60") (name "Net-(LED5-A)") (class "Default")
      (node (ref "LED5") (pin "2") (pinfunction "A_2") (pintype "bidirectional"))
      (node (ref "R19") (pin "2") (pinfunction "2_2") (pintype "passive"))
    )
    (net (code "61") (name "Net-(PS1-EN)") (class "Default")
      (node (ref "PS1") (pin "1") (pinfunction "EN_1") (pintype "bidirectional"))
      (node (ref "R36") (pin "1") (pinfunction "1_1") (pintype "passive"))
    )
    (net (code "62") (name "Net-(Q1-D)") (class "Default")
      (node (ref "BATTERY") (pin "2") (pinfunction "2_2") (pintype "passive"))
      (node (ref "Q1") (pin "3") (pinfunction "D_3") (pintype "bidirectional"))
      (node (ref "R1") (pin "1") (pinfunction "1_1") (pintype "passive"))
    )
    (net (code "63") (name "Net-(Q1-S)") (class "Default")
      (node (ref "Q1") (pin "2") (pinfunction "S_2") (pintype "bidirectional"))
      (node (ref "SW1") (pin "2") (pinfunction "2_2") (pintype "passive"))
    )
    (net (code "64") (name "Net-(Q4-B)") (class "Default")
      (node (ref "Q4") (pin "1") (pinfunction "B_1") (pintype "bidirectional"))
      (node (ref "R17") (pin "1") (pinfunction "1_1") (pintype "passive"))
      (node (ref "R18") (pin "1") (pinfunction "1_1") (pintype "passive"))
    )
    (net (code "65") (name "Net-(Q4-E)") (class "Default")
      (node (ref "C4") (pin "1") (pinfunction "1_1") (pintype "passive"))
      (node (ref "Q4") (pin "2") (pinfunction "E_2") (pintype "bidirectional"))
      (node (ref "R16") (pin "2") (pinfunction "2_2") (pintype "passive"))
      (node (ref "R17") (pin "2") (pinfunction "2_2") (pintype "passive"))
    )
    (net (code "66") (name "Net-(Q5-G)") (class "Default")
      (node (ref "Q5") (pin "1") (pinfunction "G_1") (pintype "bidirectional"))
      (node (ref "R34") (pin "2") (pinfunction "2_2") (pintype "passive"))
    )
    (net (code "67") (name "Net-(Q6-G)") (class "Default")
      (node (ref "Q6") (pin "1") (pinfunction "G_1") (pintype "bidirectional"))
      (node (ref "R35") (pin "2") (pinfunction "2_2") (pintype "passive"))
    )
    (net (code "68") (name "Net-(R14-Pad1)") (class "Default")
      (node (ref "R14") (pin "1") (pinfunction "1_1") (pintype "passive"))
      (node (ref "S1") (pin "8") (pinfunction "8_8") (pintype "passive"))
    )
    (net (code "69") (name "Net-(R25-Pad2)") (class "Default")
      (node (ref "R25") (pin "2") (pinfunction "2_2") (pintype "passive"))
      (node (ref "S2") (pin "2") (pinfunction "1_2") (pintype "passive"))
      (node (ref "S2") (pin "3") (pinfunction "1_3") (pintype "passive"))
    )
    (net (code "70") (name "Net-(R29-Pad1)") (class "Default")
      (node (ref "R29") (pin "1") (pinfunction "1_1") (pintype "passive"))
      (node (ref "R30") (pin "2") (pinfunction "2_2") (pintype "passive"))
      (node (ref "U$1") (pin "EN") (pinfunction "EN_EN") (pintype "bidirectional"))
    )
    (net (code "71") (name "Net-(R31-Pad1)") (class "Default")
      (node (ref "R31") (pin "1") (pinfunction "1_1") (pintype "passive"))
      (node (ref "U$1") (pin "POK") (pinfunction "POK_POK") (pintype "bidirectional"))
    )
    (net (code "72") (name "Net-(R37-Pad1)") (class "Default")
      (node (ref "R37") (pin "1") (pinfunction "1_1") (pintype "passive"))
      (node (ref "U$4") (pin "EN") (pinfunction "EN_EN") (pintype "bidirectional"))
    )
    (net (code "73") (name "Net-(R38-Pad1)") (class "Default")
      (node (ref "R38") (pin "1") (pinfunction "1_1") (pintype "passive"))
      (node (ref "R39") (pin "2") (pinfunction "2_2") (pintype "passive"))
      (node (ref "U$4") (pin "FB") (pinfunction "FB_FB") (pintype "bidirectional"))
    )
    (net (code "74") (name "PCM_CLK") (class "Default")
      (node (ref "IC1") (pin "76") (pinfunction "PCM_CLK_76") (pintype "bidirectional"))
    )
    (net (code "75") (name "PCM_DIN") (class "Default")
      (node (ref "IC1") (pin "74") (pinfunction "PCM_IN_74") (pintype "bidirectional"))
    )
    (net (code "76") (name "PCM_DOUT") (class "Default")
      (node (ref "IC1") (pin "73") (pinfunction "PCM_OUT_73") (pintype "bidirectional"))
    )
    (net (code "77") (name "PCM_SYNC") (class "Default")
      (node (ref "IC1") (pin "75") (pinfunction "PCM_SYNC_75") (pintype "bidirectional"))
    )
    (net (code "78") (name "PE") (class "Default")
      (node (ref "BUZZER") (pin "2") (pinfunction "2_2") (pintype "passive"))
      (node (ref "C10") (pin "2") (pinfunction "2_2") (pintype "passive"))
      (node (ref "C11") (pin "2") (pinfunction "2_2") (pintype "passive"))
      (node (ref "C13") (pin "1") (pinfunction "1_1") (pintype "passive"))
      (node (ref "C14") (pin "1") (pinfunction "1_1") (pintype "passive"))
      (node (ref "C15") (pin "2") (pinfunction "2_2") (pintype "passive"))
      (node (ref "C16") (pin "2") (pinfunction "2_2") (pintype "passive"))
      (node (ref "C17") (pin "-") (pinfunction "-_-") (pintype "passive"))
      (node (ref "C18") (pin "-") (pinfunction "-_-") (pintype "passive"))
      (node (ref "C19") (pin "2") (pinfunction "2_2") (pintype "passive"))
      (node (ref "C2") (pin "2") (pinfunction "2_2") (pintype "passive"))
      (node (ref "C20") (pin "2") (pinfunction "2_2") (pintype "passive"))
      (node (ref "C21") (pin "2") (pinfunction "2_2") (pintype "passive"))
      (node (ref "C22") (pin "2") (pinfunction "2_2") (pintype "passive"))
      (node (ref "C23") (pin "1") (pinfunction "1_1") (pintype "passive"))
      (node (ref "C24") (pin "1") (pinfunction "1_1") (pintype "passive"))
      (node (ref "C25") (pin "1") (pinfunction "1_1") (pintype "passive"))
      (node (ref "C26") (pin "1") (pinfunction "1_1") (pintype "passive"))
      (node (ref "C27") (pin "1") (pinfunction "1_1") (pintype "passive"))
      (node (ref "C28") (pin "1") (pinfunction "1_1") (pintype "passive"))
      (node (ref "C29") (pin "2") (pinfunction "2_2") (pintype "passive"))
      (node (ref "C3") (pin "2") (pinfunction "2_2") (pintype "passive"))
      (node (ref "C31") (pin "2") (pinfunction "2_2") (pintype "passive"))
      (node (ref "C32") (pin "2") (pinfunction "2_2") (pintype "passive"))
      (node (ref "C33") (pin "2") (pinfunction "2_2") (pintype "passive"))
      (node (ref "C34") (pin "2") (pinfunction "2_2") (pintype "passive"))
      (node (ref "C35") (pin "2") (pinfunction "2_2") (pintype "passive"))
      (node (ref "C36") (pin "2") (pinfunction "2_2") (pintype "passive"))
      (node (ref "C37") (pin "2") (pinfunction "2_2") (pintype "passive"))
      (node (ref "C38") (pin "2") (pinfunction "2_2") (pintype "passive"))
      (node (ref "C8") (pin "1") (pinfunction "1_1") (pintype "passive"))
      (node (ref "C9") (pin "1") (pinfunction "1_1") (pintype "passive"))
      (node (ref "D2") (pin "2") (pinfunction "GND_2") (pintype "bidirectional"))
      (node (ref "D3") (pin "2") (pinfunction "A_2") (pintype "bidirectional"))
      (node (ref "IC1") (pin "1") (pinfunction "GND_1_1") (pintype "bidirectional"))
      (node (ref "IC1") (pin "10") (pinfunction "GND_4_10") (pintype "bidirectional"))
      (node (ref "IC1") (pin "110") (pinfunction "GND_22_110") (pintype "bidirectional"))
      (node (ref "IC1") (pin "118") (pinfunction "GND_23_118") (pintype "bidirectional"))
      (node (ref "IC1") (pin "120") (pinfunction "GND_24_120") (pintype "bidirectional"))
      (node (ref "IC1") (pin "121") (pinfunction "GND_25_121") (pintype "bidirectional"))
      (node (ref "IC1") (pin "122") (pinfunction "GND_26_122") (pintype "bidirectional"))
      (node (ref "IC1") (pin "123") (pinfunction "GND_27_123") (pintype "bidirectional"))
      (node (ref "IC1") (pin "124") (pinfunction "GND_28_124") (pintype "bidirectional"))
      (node (ref "IC1") (pin "125") (pinfunction "GND_29_125") (pintype "bidirectional"))
      (node (ref "IC1") (pin "126") (pinfunction "GND_30_126") (pintype "bidirectional"))
      (node (ref "IC1") (pin "127") (pinfunction "GND_31_127") (pintype "bidirectional"))
      (node (ref "IC1") (pin "128") (pinfunction "GND_32_128") (pintype "bidirectional"))
      (node (ref "IC1") (pin "129") (pinfunction "GND_33_129") (pintype "bidirectional"))
      (node (ref "IC1") (pin "130") (pinfunction "GND_34_130") (pintype "bidirectional"))
      (node (ref "IC1") (pin "131") (pinfunction "GND_35_131") (pintype "bidirectional"))
      (node (ref "IC1") (pin "132") (pinfunction "GND_36_132") (pintype "bidirectional"))
      (node (ref "IC1") (pin "133") (pinfunction "GND_37_133") (pintype "bidirectional"))
      (node (ref "IC1") (pin "134") (pinfunction "GND_38_134") (pintype "bidirectional"))
      (node (ref "IC1") (pin "135") (pinfunction "GND_39_135") (pintype "bidirectional"))
      (node (ref "IC1") (pin "14") (pinfunction "GND_5_14") (pintype "bidirectional"))
      (node (ref "IC1") (pin "2") (pinfunction "GND_2_2") (pintype "bidirectional"))
      (node (ref "IC1") (pin "37") (pinfunction "GND_6_37") (pintype "bidirectional"))
      (node (ref "IC1") (pin "40") (pinfunction "GND_7_40") (pintype "bidirectional"))
      (node (ref "IC1") (pin "41") (pinfunction "GND_8_41") (pintype "bidirectional"))
      (node (ref "IC1") (pin "43") (pinfunction "GND_9_43") (pintype "bidirectional"))
      (node (ref "IC1") (pin "5") (pinfunction "GND_3_5") (pintype "bidirectional"))
      (node (ref "IC1") (pin "57") (pinfunction "GND_10_57") (pintype "bidirectional"))
      (node (ref "IC1") (pin "58") (pinfunction "GND_11_58") (pintype "bidirectional"))
      (node (ref "IC1") (pin "60") (pinfunction "GND_12_60") (pintype "bidirectional"))
      (node (ref "IC1") (pin "61") (pinfunction "GND_13_61") (pintype "bidirectional"))
      (node (ref "IC1") (pin "64") (pinfunction "GND_14_64") (pintype "bidirectional"))
      (node (ref "IC1") (pin "65") (pinfunction "GND_15_65") (pintype "bidirectional"))
      (node (ref "IC1") (pin "77") (pinfunction "GND_16_77") (pintype "bidirectional"))
      (node (ref "IC1") (pin "78") (pinfunction "GND_17_78") (pintype "bidirectional"))
      (node (ref "IC1") (pin "80") (pinfunction "GND_18_80") (pintype "bidirectional"))
      (node (ref "IC1") (pin "81") (pinfunction "GND_19_81") (pintype "bidirectional"))
      (node (ref "IC1") (pin "93") (pinfunction "GND_20_93") (pintype "bidirectional"))
      (node (ref "IC1") (pin "98") (pinfunction "GND_21_98") (pintype "bidirectional"))
      (node (ref "IC3") (pin "2") (pinfunction "GND_2") (pintype "bidirectional"))
      (node (ref "IC4") (pin "11") (pinfunction "GND_11") (pintype "bidirectional"))
      (node (ref "IC5") (pin "A1") (pinfunction "GND_1_A1") (pintype "bidirectional"))
      (node (ref "IC5") (pin "A12") (pinfunction "GND_2_A12") (pintype "bidirectional"))
      (node (ref "IC5") (pin "B1") (pinfunction "GND_3_B1") (pintype "bidirectional"))
      (node (ref "IC5") (pin "B12") (pinfunction "GND_4_B12") (pintype "bidirectional"))
      (node (ref "IC5") (pin "G1") (pinfunction "GND_5_G1") (pintype "bidirectional"))
      (node (ref "IC5") (pin "G2") (pinfunction "GND_6_G2") (pintype "bidirectional"))
      (node (ref "J1") (pin "2") (pinfunction "2_2") (pintype "bidirectional"))
      (node (ref "J1") (pin "3") (pinfunction "3_3") (pintype "bidirectional"))
      (node (ref "J1") (pin "4") (pinfunction "4_4") (pintype "bidirectional"))
      (node (ref "J1") (pin "5") (pinfunction "5_5") (pintype "bidirectional"))
      (node (ref "J2") (pin "2") (pinfunction "2_2") (pintype "bidirectional"))
      (node (ref "J2") (pin "3") (pinfunction "3_3") (pintype "bidirectional"))
      (node (ref "J2") (pin "4") (pinfunction "4_4") (pintype "bidirectional"))
      (node (ref "J2") (pin "5") (pinfunction "5_5") (pintype "bidirectional"))
      (node (ref "J3") (pin "C5") (pinfunction "GND_C5") (pintype "bidirectional"))
      (node (ref "LED2") (pin "1") (pinfunction "K_1") (pintype "bidirectional"))
      (node (ref "LED3") (pin "1") (pinfunction "K_1") (pintype "bidirectional"))
      (node (ref "LED4") (pin "1") (pinfunction "K_1") (pintype "bidirectional"))
      (node (ref "LED5") (pin "1") (pinfunction "K_1") (pintype "bidirectional"))
      (node (ref "MOTOR") (pin "2") (pinfunction "2_2") (pintype "passive"))
      (node (ref "PS1") (pin "2") (pinfunction "GND_2") (pintype "bidirectional"))
      (node (ref "Q2") (pin "3") (pinfunction "S2_3") (pintype "bidirectional"))
      (node (ref "R12") (pin "2") (pinfunction "2_2") (pintype "passive"))
      (node (ref "R13") (pin "1") (pinfunction "1_1") (pintype "passive"))
      (node (ref "R14") (pin "2") (pinfunction "2_2") (pintype "passive"))
      (node (ref "R2") (pin "1") (pinfunction "1_1") (pintype "passive"))
      (node (ref "R26") (pin "1") (pinfunction "1_1") (pintype "passive"))
      (node (ref "R27") (pin "1") (pinfunction "1_1") (pintype "passive"))
      (node (ref "R30") (pin "1") (pinfunction "1_1") (pintype "passive"))
      (node (ref "R33") (pin "1") (pinfunction "1_1") (pintype "passive"))
      (node (ref "R39") (pin "1") (pinfunction "1_1") (pintype "passive"))
      (node (ref "R40") (pin "1") (pinfunction "1_1") (pintype "passive"))
      (node (ref "S2") (pin "1") (pinfunction "2_1") (pintype "passive"))
      (node (ref "S2") (pin "4") (pinfunction "2_4") (pintype "passive"))
      (node (ref "SW1") (pin "1") (pinfunction "1_1") (pintype "passive"))
      (node (ref "SWITCH1") (pin "2") (pinfunction "2_2") (pintype "passive"))
      (node (ref "SWITCH2") (pin "2") (pinfunction "2_2") (pintype "passive"))
      (node (ref "U$1") (pin "GND") (pinfunction "GND_GND") (pintype "bidirectional"))
      (node (ref "U$3") (pin "GND") (pinfunction "GND1_GND") (pintype "bidirectional"))
      (node (ref "U$3") (pin "GND2") (pinfunction "GND2_GND2") (pintype "bidirectional"))
      (node (ref "U$3") (pin "GND3") (pinfunction "P_GND_GND3") (pintype "bidirectional"))
      (node (ref "U$4") (pin "GND") (pinfunction "GND_GND") (pintype "bidirectional"))
    )
    (net (code "79") (name "PWRKEY") (class "Default")
      (node (ref "C4") (pin "2") (pinfunction "2_2") (pintype "passive"))
      (node (ref "IC1") (pin "3") (pinfunction "PWRKEY_3") (pintype "bidirectional"))
      (node (ref "Q4") (pin "3") (pinfunction "C_3") (pintype "bidirectional"))
      (node (ref "R16") (pin "1") (pinfunction "1_1") (pintype "passive"))
      (node (ref "S1") (pin "1") (pinfunction "1_1") (pintype "passive"))
    )
    (net (code "80") (name "RST_EN") (class "Default")
      (node (ref "D2") (pin "3") (pinfunction "I/O4_3") (pintype "bidirectional"))
      (node (ref "J3") (pin "C2") (pinfunction "RST_C2") (pintype "bidirectional"))
      (node (ref "R10") (pin "1") (pinfunction "1_1") (pintype "passive"))
    )
    (net (code "81") (name "RST{slash}EN") (class "Default")
      (node (ref "C28") (pin "2") (pinfunction "2_2") (pintype "passive"))
      (node (ref "Q3") (pin "6") (pinfunction "C1_6") (pintype "bidirectional"))
      (node (ref "R24") (pin "2") (pinfunction "2_2") (pintype "passive"))
      (node (ref "R25") (pin "1") (pinfunction "1_1") (pintype "passive"))
      (node (ref "U$3") (pin "EN") (pinfunction "EN_EN") (pintype "bidirectional"))
    )
    (net (code "82") (name "RTS") (class "Default")
      (node (ref "Q3") (pin "1") (pinfunction "E1_1") (pintype "bidirectional"))
      (node (ref "Q3") (pin "5") (pinfunction "B2_5") (pintype "bidirectional"))
    )
    (net (code "83") (name "SCL") (class "Default")
      (node (ref "IC1") (pin "55") (pinfunction "SCL_55") (pintype "bidirectional"))
    )
    (net (code "84") (name "SDA") (class "Default")
      (node (ref "IC1") (pin "56") (pinfunction "SDA_56") (pintype "bidirectional"))
    )
    (net (code "85") (name "SIM_CLK") (class "Default")
      (node (ref "C19") (pin "1") (pinfunction "1_1") (pintype "passive"))
      (node (ref "IC1") (pin "19") (pinfunction "USIM_CLK_19") (pintype "bidirectional"))
      (node (ref "R11") (pin "2") (pinfunction "2_2") (pintype "passive"))
    )
    (net (code "86") (name "SIM_IO") (class "Default")
      (node (ref "C20") (pin "1") (pinfunction "1_1") (pintype "passive"))
      (node (ref "IC1") (pin "17") (pinfunction "USIM_DATA_17") (pintype "bidirectional"))
      (node (ref "R9") (pin "1") (pinfunction "1_1") (pintype "passive"))
    )
    (net (code "87") (name "SIM_RST") (class "Default")
      (node (ref "C21") (pin "1") (pinfunction "1_1") (pintype "passive"))
      (node (ref "IC1") (pin "18") (pinfunction "USIM_RST_18") (pintype "bidirectional"))
      (node (ref "R10") (pin "2") (pinfunction "2_2") (pintype "passive"))
    )
    (net (code "88") (name "STATUS") (class "Default")
      (node (ref "IC1") (pin "49") (pinfunction "STATUS_49") (pintype "bidirectional"))
      (node (ref "R19") (pin "1") (pinfunction "1_1") (pintype "passive"))
    )
    (net (code "89") (name "S_VN{slash}39") (class "Default")
      (node (ref "U$3") (pin "SENSOR_VN") (pinfunction "SENSR_VN_SENSOR_VN") (pintype "bidirectional"))
    )
    (net (code "90") (name "S_VP") (class "Default")
      (node (ref "U$3") (pin "SENSOR_VP") (pinfunction "SENSR_VP_SENSOR_VP") (pintype "bidirectional"))
    )
    (net (code "91") (name "U0RXD") (class "Default")
      (node (ref "R4") (pin "2") (pinfunction "2_2") (pintype "passive"))
      (node (ref "U$3") (pin "RXD0") (pinfunction "RXD0_RXD0") (pintype "bidirectional"))
    )
    (net (code "92") (name "U0TXD") (class "Default")
      (node (ref "R5") (pin "2") (pinfunction "2_2") (pintype "passive"))
      (node (ref "U$3") (pin "TXD0") (pinfunction "TXD0_TXD0") (pintype "bidirectional"))
    )
    (net (code "93") (name "UART_DTR") (class "Default")
      (node (ref "IC1") (pin "72") (pinfunction "DTR_72") (pintype "bidirectional"))
      (node (ref "IC4") (pin "6") (pinfunction "A5_6") (pintype "bidirectional"))
    )
    (net (code "94") (name "UART_RI") (class "Default")
      (node (ref "IC1") (pin "69") (pinfunction "RI_69") (pintype "bidirectional"))
      (node (ref "IC4") (pin "8") (pinfunction "A7_8") (pintype "bidirectional"))
    )
    (net (code "95") (name "UART_RXD") (class "Default")
      (node (ref "IC4") (pin "3") (pinfunction "A2_3") (pintype "bidirectional"))
    )
    (net (code "96") (name "UART_TXD") (class "Default")
      (node (ref "IC1") (pin "71") (pinfunction "TXD_71") (pintype "bidirectional"))
      (node (ref "IC4") (pin "1") (pinfunction "A1_1") (pintype "bidirectional"))
    )
    (net (code "97") (name "USB_DM") (class "Default")
      (node (ref "IC1") (pin "12") (pinfunction "USB_DN_12") (pintype "bidirectional"))
    )
    (net (code "98") (name "USB_DP") (class "Default")
      (node (ref "IC1") (pin "13") (pinfunction "USB_DP_13") (pintype "bidirectional"))
    )
    (net (code "99") (name "USB_VBUS") (class "Default")
      (node (ref "IC1") (pin "11") (pinfunction "USB_VBUS_11") (pintype "bidirectional"))
    )
    (net (code "100") (name "VBAT-") (class "Default")
      (node (ref "Q2") (pin "1") (pinfunction "S1_1") (pintype "bidirectional"))
    )
    (net (code "101") (name "VBUS") (class "Default")
      (node (ref "C29") (pin "1") (pinfunction "1_1") (pintype "passive"))
      (node (ref "D1") (pin "2") (pinfunction "A_2") (pintype "bidirectional"))
      (node (ref "IC5") (pin "A4") (pinfunction "VBUS_1_A4") (pintype "bidirectional"))
      (node (ref "IC5") (pin "A9") (pinfunction "VBUS_2_A9") (pintype "bidirectional"))
      (node (ref "IC5") (pin "B4") (pinfunction "VBUS_3_B4") (pintype "bidirectional"))
      (node (ref "R29") (pin "2") (pinfunction "2_2") (pintype "passive"))
      (node (ref "R34") (pin "1") (pinfunction "1_1") (pintype "passive"))
      (node (ref "R35") (pin "1") (pinfunction "1_1") (pintype "passive"))
      (node (ref "U$1") (pin "VIN") (pinfunction "VIN_VIN") (pintype "bidirectional"))
    )
    (net (code "102") (name "VCC3V3") (class "Default")
      (node (ref "C24") (pin "2") (pinfunction "2_2") (pintype "passive"))
      (node (ref "C26") (pin "2") (pinfunction "2_2") (pintype "passive"))
      (node (ref "C27") (pin "2") (pinfunction "2_2") (pintype "passive"))
      (node (ref "C33") (pin "1") (pinfunction "1_1") (pintype "passive"))
      (node (ref "IC4") (pin "19") (pinfunction "VCCB_19") (pintype "bidirectional"))
      (node (ref "PS1") (pin "4") (pinfunction "OUT_4") (pintype "bidirectional"))
      (node (ref "R20") (pin "2") (pinfunction "2_2") (pintype "passive"))
      (node (ref "R21") (pin "2") (pinfunction "2_2") (pintype "passive"))
      (node (ref "R22") (pin "2") (pinfunction "2_2") (pintype "passive"))
      (node (ref "R23") (pin "2") (pinfunction "2_2") (pintype "passive"))
      (node (ref "R24") (pin "1") (pinfunction "1_1") (pintype "passive"))
      (node (ref "U$3") (pin "VDD33") (pinfunction "3V3_VDD33") (pintype "bidirectional"))
    )
    (net (code "103") (name "VCC_4V2") (class "Default")
      (node (ref "C30") (pin "1") (pinfunction "1_1") (pintype "passive"))
      (node (ref "C31") (pin "1") (pinfunction "1_1") (pintype "passive"))
      (node (ref "C32") (pin "1") (pinfunction "1_1") (pintype "passive"))
      (node (ref "D5") (pin "2") (pinfunction "A_2") (pintype "bidirectional"))
      (node (ref "L2") (pin "2") (pinfunction "2_2") (pintype "bidirectional"))
      (node (ref "R31") (pin "2") (pinfunction "2_2") (pintype "passive"))
      (node (ref "R32") (pin "2") (pinfunction "2_2") (pintype "passive"))
    )
    (net (code "104") (name "VCC_BAT") (class "Default")
      (node (ref "R3") (pin "2") (pinfunction "2_2") (pintype "passive"))
    )
    (net (code "106") (name "VCC_UART") (class "Default")
      (node (ref "C2") (pin "1") (pinfunction "1_1") (pintype "passive"))
      (node (ref "C3") (pin "1") (pinfunction "1_1") (pintype "passive"))
      (node (ref "IC3") (pin "5") (pinfunction "VIO_5") (pintype "bidirectional"))
      (node (ref "IC3") (pin "6") (pinfunction "VDD_6") (pintype "bidirectional"))
    )
    (net (code "107") (name "VDD_1V8") (class "Default")
      (node (ref "C23") (pin "2") (pinfunction "2_2") (pintype "passive"))
      (node (ref "IC1") (pin "15") (pinfunction "VDD_1V8_15") (pintype "bidirectional"))
      (node (ref "IC4") (pin "10") (pinfunction "OE_10") (pintype "bidirectional"))
      (node (ref "IC4") (pin "2") (pinfunction "VCCA_2") (pintype "bidirectional"))
    )
    (net (code "108") (name "VDD_3V") (class "Default")
      (node (ref "IC1") (pin "44") (pinfunction "VDD_AUX_44") (pintype "bidirectional"))
      (node (ref "R8") (pin "1") (pinfunction "1_1") (pintype "passive"))
    )
    (net (code "109") (name "VDD_4V2") (class "Default")
      (node (ref "C37") (pin "1") (pinfunction "1_1") (pintype "passive"))
      (node (ref "C38") (pin "1") (pinfunction "1_1") (pintype "passive"))
      (node (ref "D6") (pin "1") (pinfunction "K_1") (pintype "bidirectional"))
      (node (ref "Q6") (pin "3") (pinfunction "D_3") (pintype "bidirectional"))
      (node (ref "R38") (pin "2") (pinfunction "2_2") (pintype "passive"))
      (node (ref "R40") (pin "2") (pinfunction "2_2") (pintype "passive"))
    )
    (net (code "110") (name "VSIM") (class "Default")
      (node (ref "C22") (pin "1") (pinfunction "1_1") (pintype "passive"))
      (node (ref "D2") (pin "4") (pinfunction "I/O5_4") (pintype "bidirectional"))
      (node (ref "IC1") (pin "20") (pinfunction "USIM_VDD_20") (pintype "bidirectional"))
      (node (ref "J3") (pin "C1") (pinfunction "VCC_C1") (pintype "bidirectional"))
    )
    (net (code "111") (name "VVBAT") (class "Default")
      (node (ref "C35") (pin "1") (pinfunction "1_1") (pintype "passive"))
      (node (ref "C36") (pin "1") (pinfunction "1_1") (pintype "passive"))
      (node (ref "L3") (pin "1") (pinfunction "1_1") (pintype "bidirectional"))
      (node (ref "Q5") (pin "3") (pinfunction "D_3") (pintype "bidirectional"))
      (node (ref "R28") (pin "2") (pinfunction "2_2") (pintype "passive"))
      (node (ref "R37") (pin "2") (pinfunction "2_2") (pintype "passive"))
    )
    (net (code "112") (name "V_BAT") (class "Default")
      (node (ref "Q5") (pin "2") (pinfunction "S_2") (pintype "bidirectional"))
    )
    (net (code "113") (name "unconnected-(D2-I{slash}O2-Pad6)") (class "Default")
      (node (ref "D2") (pin "6") (pinfunction "I/O2_6") (pintype "bidirectional"))
    )
    (net (code "114") (name "unconnected-(IC1-ADC1-Pad47)") (class "Default")
      (node (ref "IC1") (pin "47") (pinfunction "ADC1_47") (pintype "bidirectional"))
    )
    (net (code "115") (name "unconnected-(IC1-ADC2-Pad46)") (class "Default")
      (node (ref "IC1") (pin "46") (pinfunction "ADC2_46") (pintype "bidirectional"))
    )
    (net (code "116") (name "unconnected-(IC1-AUX_ANT-Pad59)") (class "Default")
      (node (ref "IC1") (pin "59") (pinfunction "AUX_ANT_59") (pintype "bidirectional"))
    )
    (net (code "117") (name "unconnected-(IC1-COEX3●~{}-Pad86)") (class "Default")
      (node (ref "IC1") (pin "86") (pinfunction "COEX3●~{}_86") (pintype "bidirectional"))
    )
    (net (code "118") (name "unconnected-(IC1-CTS-Pad67)") (class "Default")
      (node (ref "IC1") (pin "67") (pinfunction "CTS_67") (pintype "bidirectional"))
    )
    (net (code "119") (name "unconnected-(IC1-DBG_RXD-Pad106)") (class "Default")
      (node (ref "IC1") (pin "106") (pinfunction "DBG_RXD_106") (pintype "bidirectional"))
    )
    (net (code "120") (name "unconnected-(IC1-DBG_TXD-Pad42)") (class "Default")
      (node (ref "IC1") (pin "42") (pinfunction "DBG_TXD_42") (pintype "bidirectional"))
    )
    (net (code "121") (name "unconnected-(IC1-DCD-Pad70)") (class "Default")
      (node (ref "IC1") (pin "70") (pinfunction "DCD_70") (pintype "bidirectional"))
    )
    (net (code "122") (name "unconnected-(IC1-GPIO1-Pad96)") (class "Default")
      (node (ref "IC1") (pin "96") (pinfunction "GPIO1_96") (pintype "bidirectional"))
    )
    (net (code "123") (name "unconnected-(IC1-GPIO2-Pad95)") (class "Default")
      (node (ref "IC1") (pin "95") (pinfunction "GPIO2_95") (pintype "bidirectional"))
    )
    (net (code "124") (name "unconnected-(IC1-GPIO4-Pad94)") (class "Default")
      (node (ref "IC1") (pin "94") (pinfunction "GPIO4_94") (pintype "bidirectional"))
    )
    (net (code "125") (name "unconnected-(IC1-GPIO41~{}-Pad52)") (class "Default")
      (node (ref "IC1") (pin "52") (pinfunction "GPIO41~{}_52") (pintype "bidirectional"))
    )
    (net (code "126") (name "unconnected-(IC1-GPIO43-Pad50)") (class "Default")
      (node (ref "IC1") (pin "50") (pinfunction "GPIO43_50") (pintype "bidirectional"))
    )
    (net (code "127") (name "unconnected-(IC1-GPIO77~{}-Pad87)") (class "Default")
      (node (ref "IC1") (pin "87") (pinfunction "GPIO77~{}_87") (pintype "bidirectional"))
    )
    (net (code "128") (name "unconnected-(IC1-GPIO_19-Pad119)") (class "Default")
      (node (ref "IC1") (pin "119") (pinfunction "GPIO_19_119") (pintype "bidirectional"))
    )
    (net (code "129") (name "unconnected-(IC1-GPIO_54-Pad97)") (class "Default")
      (node (ref "IC1") (pin "97") (pinfunction "GPIO_54_97") (pintype "bidirectional"))
    )
    (net (code "130") (name "unconnected-(IC1-HSIC_DATA-Pad36)") (class "Default")
      (node (ref "IC1") (pin "36") (pinfunction "HSIC_DATA_36") (pintype "bidirectional"))
    )
    (net (code "131") (name "unconnected-(IC1-HSIC_STROBE-Pad35)") (class "Default")
      (node (ref "IC1") (pin "35") (pinfunction "HSIC_STROBE_35") (pintype "bidirectional"))
    )
    (net (code "132") (name "unconnected-(IC1-ISINK-Pad45)") (class "Default")
      (node (ref "IC1") (pin "45") (pinfunction "ISINK_45") (pintype "bidirectional"))
    )
    (net (code "133") (name "unconnected-(IC1-RESERVED_1-Pad88)") (class "Default")
      (node (ref "IC1") (pin "88") (pinfunction "RESERVED_1_88") (pintype "bidirectional"))
    )
    (net (code "134") (name "unconnected-(IC1-RESERVED_2-Pad89)") (class "Default")
      (node (ref "IC1") (pin "89") (pinfunction "RESERVED_2_89") (pintype "bidirectional"))
    )
    (net (code "135") (name "unconnected-(IC1-RESERVED_3-Pad90)") (class "Default")
      (node (ref "IC1") (pin "90") (pinfunction "RESERVED_3_90") (pintype "bidirectional"))
    )
    (net (code "136") (name "unconnected-(IC1-RESERVED_4-Pad91)") (class "Default")
      (node (ref "IC1") (pin "91") (pinfunction "RESERVED_4_91") (pintype "bidirectional"))
    )
    (net (code "137") (name "unconnected-(IC1-RESERVED_5-Pad92)") (class "Default")
      (node (ref "IC1") (pin "92") (pinfunction "RESERVED_5_92") (pintype "bidirectional"))
    )
    (net (code "138") (name "unconnected-(IC1-RESERVED_6-Pad99)") (class "Default")
      (node (ref "IC1") (pin "99") (pinfunction "RESERVED_6_99") (pintype "bidirectional"))
    )
    (net (code "139") (name "unconnected-(IC1-RESERVED_7-Pad100)") (class "Default")
      (node (ref "IC1") (pin "100") (pinfunction "RESERVED_7_100") (pintype "bidirectional"))
    )
    (net (code "140") (name "unconnected-(IC1-RESERVED_8-Pad101)") (class "Default")
      (node (ref "IC1") (pin "101") (pinfunction "RESERVED_8_101") (pintype "bidirectional"))
    )
    (net (code "141") (name "unconnected-(IC1-RESERVED_9-Pad102)") (class "Default")
      (node (ref "IC1") (pin "102") (pinfunction "RESERVED_9_102") (pintype "bidirectional"))
    )
    (net (code "142") (name "unconnected-(IC1-RESERVED_10-Pad103)") (class "Default")
      (node (ref "IC1") (pin "103") (pinfunction "RESERVED_10_103") (pintype "bidirectional"))
    )
    (net (code "143") (name "unconnected-(IC1-RESERVED_11-Pad104)") (class "Default")
      (node (ref "IC1") (pin "104") (pinfunction "RESERVED_11_104") (pintype "bidirectional"))
    )
    (net (code "144") (name "unconnected-(IC1-RESERVED_12-Pad105)") (class "Default")
      (node (ref "IC1") (pin "105") (pinfunction "RESERVED_12_105") (pintype "bidirectional"))
    )
    (net (code "145") (name "unconnected-(IC1-RESERVED_13-Pad107)") (class "Default")
      (node (ref "IC1") (pin "107") (pinfunction "RESERVED_13_107") (pintype "bidirectional"))
    )
    (net (code "146") (name "unconnected-(IC1-RESERVED_14-Pad111)") (class "Default")
      (node (ref "IC1") (pin "111") (pinfunction "RESERVED_14_111") (pintype "bidirectional"))
    )
    (net (code "147") (name "unconnected-(IC1-RESET-Pad4)") (class "Default")
      (node (ref "IC1") (pin "4") (pinfunction "RESET_4") (pintype "bidirectional"))
    )
    (net (code "148") (name "unconnected-(IC1-RTS-Pad66)") (class "Default")
      (node (ref "IC1") (pin "66") (pinfunction "RTS_66") (pintype "bidirectional"))
    )
    (net (code "149") (name "unconnected-(IC1-SDIO_CLK-Pad32)") (class "Default")
      (node (ref "IC1") (pin "32") (pinfunction "SDIO_CLK_32") (pintype "bidirectional"))
    )
    (net (code "150") (name "unconnected-(IC1-SDIO_CMD-Pad29)") (class "Default")
      (node (ref "IC1") (pin "29") (pinfunction "SDIO_CMD_29") (pintype "bidirectional"))
    )
    (net (code "151") (name "unconnected-(IC1-SDIO_DATA0-Pad30)") (class "Default")
      (node (ref "IC1") (pin "30") (pinfunction "SDIO_DATA0_30") (pintype "bidirectional"))
    )
    (net (code "152") (name "unconnected-(IC1-SDIO_DATA1-Pad27)") (class "Default")
      (node (ref "IC1") (pin "27") (pinfunction "SDIO_DATA1_27") (pintype "bidirectional"))
    )
    (net (code "153") (name "unconnected-(IC1-SDIO_DATA2-Pad28)") (class "Default")
      (node (ref "IC1") (pin "28") (pinfunction "SDIO_DATA2_28") (pintype "bidirectional"))
    )
    (net (code "154") (name "unconnected-(IC1-SDIO_DATA3-Pad31)") (class "Default")
      (node (ref "IC1") (pin "31") (pinfunction "SDIO_DATA3_31") (pintype "bidirectional"))
    )
    (net (code "155") (name "unconnected-(IC1-SD_CLK-Pad26)") (class "Default")
      (node (ref "IC1") (pin "26") (pinfunction "SD_CLK_26") (pintype "bidirectional"))
    )
    (net (code "156") (name "unconnected-(IC1-SD_CMD-Pad21)") (class "Default")
      (node (ref "IC1") (pin "21") (pinfunction "SD_CMD_21") (pintype "bidirectional"))
    )
    (net (code "157") (name "unconnected-(IC1-SD_DATA0-Pad22)") (class "Default")
      (node (ref "IC1") (pin "22") (pinfunction "SD_DATA0_22") (pintype "bidirectional"))
    )
    (net (code "158") (name "unconnected-(IC1-SD_DATA1-Pad23)") (class "Default")
      (node (ref "IC1") (pin "23") (pinfunction "SD_DATA1_23") (pintype "bidirectional"))
    )
    (net (code "159") (name "unconnected-(IC1-SD_DATA2-Pad24)") (class "Default")
      (node (ref "IC1") (pin "24") (pinfunction "SD_DATA2_24") (pintype "bidirectional"))
    )
    (net (code "160") (name "unconnected-(IC1-SD_DATA3-Pad25)") (class "Default")
      (node (ref "IC1") (pin "25") (pinfunction "SD_DATA3_25") (pintype "bidirectional"))
    )
    (net (code "161") (name "unconnected-(IC1-SD_DET-Pad48)") (class "Default")
      (node (ref "IC1") (pin "48") (pinfunction "SD_DET_48") (pintype "bidirectional"))
    )
    (net (code "162") (name "unconnected-(IC1-SGMII_INT_N-Pad109)") (class "Default")
      (node (ref "IC1") (pin "109") (pinfunction "SGMII_INT_N_109") (pintype "bidirectional"))
    )
    (net (code "163") (name "unconnected-(IC1-SGMII_MDC-Pad117)") (class "Default")
      (node (ref "IC1") (pin "117") (pinfunction "SGMII_MDC_117") (pintype "bidirectional"))
    )
    (net (code "164") (name "unconnected-(IC1-SGMII_MDIO-Pad116)") (class "Default")
      (node (ref "IC1") (pin "116") (pinfunction "SGMII_MDIO_116") (pintype "bidirectional"))
    )
    (net (code "165") (name "unconnected-(IC1-SGMII_RST_N-Pad108)") (class "Default")
      (node (ref "IC1") (pin "108") (pinfunction "SGMII_RST_N_108") (pintype "bidirectional"))
    )
    (net (code "166") (name "unconnected-(IC1-SGMII_RX_M-Pad113)") (class "Default")
      (node (ref "IC1") (pin "113") (pinfunction "SGMII_RX_M_113") (pintype "bidirectional"))
    )
    (net (code "167") (name "unconnected-(IC1-SGMII_RX_P-Pad112)") (class "Default")
      (node (ref "IC1") (pin "112") (pinfunction "SGMII_RX_P_112") (pintype "bidirectional"))
    )
    (net (code "168") (name "unconnected-(IC1-SGMII_TX_M-Pad114)") (class "Default")
      (node (ref "IC1") (pin "114") (pinfunction "SGMII_TX_M_114") (pintype "bidirectional"))
    )
    (net (code "169") (name "unconnected-(IC1-SGMII_TX_P-Pad115)") (class "Default")
      (node (ref "IC1") (pin "115") (pinfunction "SGMII_TX_P_115") (pintype "bidirectional"))
    )
    (net (code "170") (name "unconnected-(IC1-USB_ID-Pad16)") (class "Default")
      (node (ref "IC1") (pin "16") (pinfunction "USB_ID_16") (pintype "bidirectional"))
    )
    (net (code "171") (name "unconnected-(IC1-USIM_DET~{}-Pad53)") (class "Default")
      (node (ref "IC1") (pin "53") (pinfunction "USIM_DET~{}_53") (pintype "bidirectional"))
    )
    (net (code "172") (name "unconnected-(IC1-~{COEX2}-Pad84)") (class "Default")
      (node (ref "IC1") (pin "84") (pinfunction "~{COEX2}_84") (pintype "bidirectional"))
    )
    (net (code "173") (name "unconnected-(IC1-~{GPIO3}-Pad33)") (class "Default")
      (node (ref "IC1") (pin "33") (pinfunction "~{GPIO3}_33") (pintype "bidirectional"))
    )
    (net (code "174") (name "unconnected-(IC1-~{GPIO6}-Pad34)") (class "Default")
      (node (ref "IC1") (pin "34") (pinfunction "~{GPIO6}_34") (pintype "bidirectional"))
    )
    (net (code "175") (name "unconnected-(IC1-~{SPI_CLK}-Pad6)") (class "Default")
      (node (ref "IC1") (pin "6") (pinfunction "~{SPI_CLK}_6") (pintype "bidirectional"))
    )
    (net (code "176") (name "unconnected-(IC1-~{SPI_CS}-Pad9)") (class "Default")
      (node (ref "IC1") (pin "9") (pinfunction "~{SPI_CS}_9") (pintype "bidirectional"))
    )
    (net (code "177") (name "unconnected-(IC1-~{SPI_MISO}-Pad7)") (class "Default")
      (node (ref "IC1") (pin "7") (pinfunction "~{SPI_MISO}_7") (pintype "bidirectional"))
    )
    (net (code "178") (name "unconnected-(IC1-~{SPI_MOSI}-Pad8)") (class "Default")
      (node (ref "IC1") (pin "8") (pinfunction "~{SPI_MOSI}_8") (pintype "bidirectional"))
    )
    (net (code "179") (name "unconnected-(IC1-~{●COEX1}-Pad83)") (class "Default")
      (node (ref "IC1") (pin "83") (pinfunction "~{●COEX1}_83") (pintype "bidirectional"))
    )
    (net (code "180") (name "unconnected-(IC2-NC-Pad4)") (class "Default")
      (node (ref "IC2") (pin "4") (pinfunction "NC_4") (pintype "no_connect"))
    )
    (net (code "181") (name "unconnected-(IC3-CTS-Pad18)") (class "Default")
      (node (ref "IC3") (pin "18") (pinfunction "CTS_18") (pintype "bidirectional"))
    )
    (net (code "182") (name "unconnected-(IC3-D+-Pad3)") (class "Default")
      (node (ref "IC3") (pin "3") (pinfunction "D+_3") (pintype "bidirectional"))
    )
    (net (code "183") (name "unconnected-(IC3-D--Pad4)") (class "Default")
      (node (ref "IC3") (pin "4") (pinfunction "D-_4") (pintype "bidirectional"))
    )
    (net (code "184") (name "unconnected-(IC3-DCD-Pad24)") (class "Default")
      (node (ref "IC3") (pin "24") (pinfunction "DCD_24") (pintype "bidirectional"))
    )
    (net (code "185") (name "unconnected-(IC3-DSR-Pad22)") (class "Default")
      (node (ref "IC3") (pin "22") (pinfunction "DSR_22") (pintype "bidirectional"))
    )
    (net (code "186") (name "unconnected-(IC3-EP-Pad25)") (class "Default")
      (node (ref "IC3") (pin "25") (pinfunction "EP_25") (pintype "bidirectional"))
    )
    (net (code "187") (name "unconnected-(IC3-GPIO.0-Pad14)") (class "Default")
      (node (ref "IC3") (pin "14") (pinfunction "GPIO.0_14") (pintype "bidirectional"))
    )
    (net (code "188") (name "unconnected-(IC3-GPIO.1-Pad13)") (class "Default")
      (node (ref "IC3") (pin "13") (pinfunction "GPIO.1_13") (pintype "bidirectional"))
    )
    (net (code "189") (name "unconnected-(IC3-GPIO.2-Pad12)") (class "Default")
      (node (ref "IC3") (pin "12") (pinfunction "GPIO.2_12") (pintype "bidirectional"))
    )
    (net (code "190") (name "unconnected-(IC3-GPIO.3-Pad11)") (class "Default")
      (node (ref "IC3") (pin "11") (pinfunction "GPIO.3_11") (pintype "bidirectional"))
    )
    (net (code "191") (name "unconnected-(IC3-NC-Pad10)") (class "Default")
      (node (ref "IC3") (pin "10") (pinfunction "NC_10") (pintype "no_connect"))
    )
    (net (code "192") (name "unconnected-(IC3-RI-Pad1)") (class "Default")
      (node (ref "IC3") (pin "1") (pinfunction "RI_1") (pintype "bidirectional"))
    )
    (net (code "193") (name "unconnected-(IC3-RTS-Pad19)") (class "Default")
      (node (ref "IC3") (pin "19") (pinfunction "RTS_19") (pintype "bidirectional"))
    )
    (net (code "194") (name "unconnected-(IC3-SUSPEND-Pad17)") (class "Default")
      (node (ref "IC3") (pin "17") (pinfunction "SUSPEND_17") (pintype "bidirectional"))
    )
    (net (code "195") (name "unconnected-(IC3-VPP-Pad16)") (class "Default")
      (node (ref "IC3") (pin "16") (pinfunction "VPP_16") (pintype "bidirectional"))
    )
    (net (code "196") (name "unconnected-(IC3-~{RST}-Pad9)") (class "Default")
      (node (ref "IC3") (pin "9") (pinfunction "~{RST}_9") (pintype "bidirectional"))
    )
    (net (code "197") (name "unconnected-(IC3-~{SUSPEND}-Pad15)") (class "Default")
      (node (ref "IC3") (pin "15") (pinfunction "~{SUSPEND}_15") (pintype "bidirectional"))
    )
    (net (code "198") (name "unconnected-(IC4-A3-Pad4)") (class "Default")
      (node (ref "IC4") (pin "4") (pinfunction "A3_4") (pintype "bidirectional"))
    )
    (net (code "199") (name "unconnected-(IC4-A6-Pad7)") (class "Default")
      (node (ref "IC4") (pin "7") (pinfunction "A6_7") (pintype "bidirectional"))
    )
    (net (code "200") (name "unconnected-(IC4-B3-Pad17)") (class "Default")
      (node (ref "IC4") (pin "17") (pinfunction "B3_17") (pintype "bidirectional"))
    )
    (net (code "201") (name "unconnected-(IC4-B6-Pad14)") (class "Default")
      (node (ref "IC4") (pin "14") (pinfunction "B6_14") (pintype "bidirectional"))
    )
    (net (code "202") (name "unconnected-(IC4-EP-Pad21)") (class "Default")
      (node (ref "IC4") (pin "21") (pinfunction "EP_21") (pintype "bidirectional"))
    )
    (net (code "203") (name "unconnected-(IC5-CC1-PadA5)") (class "Default")
      (node (ref "IC5") (pin "A5") (pinfunction "CC1_A5") (pintype "bidirectional"))
    )
    (net (code "204") (name "unconnected-(IC5-CC2-PadB5)") (class "Default")
      (node (ref "IC5") (pin "B5") (pinfunction "CC2_B5") (pintype "bidirectional"))
    )
    (net (code "205") (name "unconnected-(IC5-DN1-PadA7)") (class "Default")
      (node (ref "IC5") (pin "A7") (pinfunction "DN1_A7") (pintype "bidirectional"))
    )
    (net (code "206") (name "unconnected-(IC5-DN2-PadB7)") (class "Default")
      (node (ref "IC5") (pin "B7") (pinfunction "DN2_B7") (pintype "bidirectional"))
    )
    (net (code "207") (name "unconnected-(IC5-DP1-PadA6)") (class "Default")
      (node (ref "IC5") (pin "A6") (pinfunction "DP1_A6") (pintype "bidirectional"))
    )
    (net (code "208") (name "unconnected-(IC5-DP2-PadB6)") (class "Default")
      (node (ref "IC5") (pin "B6") (pinfunction "DP2_B6") (pintype "bidirectional"))
    )
    (net (code "209") (name "unconnected-(IC5-PadMH1)") (class "Default")
      (node (ref "IC5") (pin "MH1") (pinfunction "MH1_MH1") (pintype "bidirectional"))
    )
    (net (code "210") (name "unconnected-(IC5-PadMH2)") (class "Default")
      (node (ref "IC5") (pin "MH2") (pinfunction "MH2_MH2") (pintype "bidirectional"))
    )
    (net (code "211") (name "unconnected-(IC5-PadMH3)") (class "Default")
      (node (ref "IC5") (pin "MH3") (pinfunction "MH3_MH3") (pintype "bidirectional"))
    )
    (net (code "212") (name "unconnected-(IC5-PadMH4)") (class "Default")
      (node (ref "IC5") (pin "MH4") (pinfunction "MH4_MH4") (pintype "bidirectional"))
    )
    (net (code "213") (name "unconnected-(IC5-PadMP1)") (class "Default")
      (node (ref "IC5") (pin "MP1") (pinfunction "MP1_MP1") (pintype "bidirectional"))
    )
    (net (code "214") (name "unconnected-(IC5-PadMP2)") (class "Default")
      (node (ref "IC5") (pin "MP2") (pinfunction "MP2_MP2") (pintype "bidirectional"))
    )
    (net (code "215") (name "unconnected-(IC5-SBU1-PadA8)") (class "Default")
      (node (ref "IC5") (pin "A8") (pinfunction "SBU1_A8") (pintype "bidirectional"))
    )
    (net (code "216") (name "unconnected-(IC5-SSRXN1-PadB10)") (class "Default")
      (node (ref "IC5") (pin "B10") (pinfunction "SSRXN1_B10") (pintype "bidirectional"))
    )
    (net (code "217") (name "unconnected-(IC5-SSRXN2-PadA10)") (class "Default")
      (node (ref "IC5") (pin "A10") (pinfunction "SSRXN2_A10") (pintype "bidirectional"))
    )
    (net (code "218") (name "unconnected-(IC5-SSRXP1-PadB11)") (class "Default")
      (node (ref "IC5") (pin "B11") (pinfunction "SSRXP1_B11") (pintype "bidirectional"))
    )
    (net (code "219") (name "unconnected-(IC5-SSRXP2-PadA11)") (class "Default")
      (node (ref "IC5") (pin "A11") (pinfunction "SSRXP2_A11") (pintype "bidirectional"))
    )
    (net (code "220") (name "unconnected-(IC5-SSTXN1-PadA3)") (class "Default")
      (node (ref "IC5") (pin "A3") (pinfunction "SSTXN1_A3") (pintype "bidirectional"))
    )
    (net (code "221") (name "unconnected-(IC5-SSTXN2-PadB3)") (class "Default")
      (node (ref "IC5") (pin "B3") (pinfunction "SSTXN2_B3") (pintype "bidirectional"))
    )
    (net (code "222") (name "unconnected-(IC5-SSTXP1-PadA2)") (class "Default")
      (node (ref "IC5") (pin "A2") (pinfunction "SSTXP1_A2") (pintype "bidirectional"))
    )
    (net (code "223") (name "unconnected-(IC5-SSTXP2-PadB2)") (class "Default")
      (node (ref "IC5") (pin "B2") (pinfunction "SSTXP2_B2") (pintype "bidirectional"))
    )
    (net (code "224") (name "unconnected-(IC5-VBUS_4-PadB9)") (class "Default")
      (node (ref "IC5") (pin "B9") (pinfunction "VBUS_4_B9") (pintype "bidirectional"))
    )
    (net (code "225") (name "unconnected-(J3-VPP-PadC6)") (class "Default")
      (node (ref "J3") (pin "C6") (pinfunction "VPP_C6") (pintype "bidirectional"))
    )
    (net (code "226") (name "unconnected-(PS1-NC-Pad5)") (class "Default")
      (node (ref "PS1") (pin "5") (pinfunction "NC_5") (pintype "no_connect"))
    )
    (net (code "227") (name "unconnected-(Q2-1{slash}D2-Pad2)") (class "Default")
      (node (ref "Q2") (pin "2") (pinfunction "1/D2_2") (pintype "bidirectional"))
    )
    (net (code "228") (name "unconnected-(Q2-D1{slash}D2-Pad5)") (class "Default")
      (node (ref "Q2") (pin "5") (pinfunction "D1/D2_5") (pintype "bidirectional"))
    )
    (net (code "229") (name "unconnected-(R9-Pad2)") (class "Default")
      (node (ref "R9") (pin "2") (pinfunction "2_2") (pintype "passive"))
    )
    (net (code "230") (name "unconnected-(S1-Pad2)") (class "Default")
      (node (ref "S1") (pin "2") (pinfunction "2_2") (pintype "passive"))
    )
    (net (code "231") (name "unconnected-(S1-Pad7)") (class "Default")
      (node (ref "S1") (pin "7") (pinfunction "7_7") (pintype "passive"))
    )
    (net (code "232") (name "unconnected-(U$3-GND3-PadGND_2)") (class "Default")
      (node (ref "U$3") (pin "GND_2") (pinfunction "GND3_GND_2") (pintype "bidirectional"))
    )
    (net (code "233") (name "unconnected-(U$3-NC-PadNC0)") (class "Default")
      (node (ref "U$3") (pin "NC0") (pinfunction "NC_NC0") (pintype "bidirectional"))
    )
    (net (code "234") (name "unconnected-(U$3-PadCLK)") (class "Default")
      (node (ref "U$3") (pin "CLK") (pinfunction "CLK_CLK") (pintype "bidirectional"))
    )
    (net (code "235") (name "unconnected-(U$3-PadCMD)") (class "Default")
      (node (ref "U$3") (pin "CMD") (pinfunction "CMD_CMD") (pintype "bidirectional"))
    )
    (net (code "236") (name "unconnected-(U$3-PadNC1)") (class "Default")
      (node (ref "U$3") (pin "NC1") (pinfunction "NC1_NC1") (pintype "bidirectional"))
    )
    (net (code "237") (name "unconnected-(U$3-PadNC2)") (class "Default")
      (node (ref "U$3") (pin "NC2") (pinfunction "NC2_NC2") (pintype "bidirectional"))
    )
    (net (code "238") (name "unconnected-(U$3-PadSD0)") (class "Default")
      (node (ref "U$3") (pin "SD0") (pinfunction "SD0_SD0") (pintype "bidirectional"))
    )
    (net (code "239") (name "unconnected-(U$3-PadSD1)") (class "Default")
      (node (ref "U$3") (pin "SD1") (pinfunction "SD1_SD1") (pintype "bidirectional"))
    )
    (net (code "240") (name "unconnected-(U$3-PadSD2)") (class "Default")
      (node (ref "U$3") (pin "SD2") (pinfunction "SD2_SD2") (pintype "bidirectional"))
    )
    (net (code "241") (name "unconnected-(U$3-PadSD3)") (class "Default")
      (node (ref "U$3") (pin "SD3") (pinfunction "SD3_SD3") (pintype "bidirectional"))
    )
    (net (code "242") (name "unconnected-(U$4-IN-PadVIN)") (class "Default")
      (node (ref "U$4") (pin "VIN") (pinfunction "IN_VIN") (pintype "bidirectional"))
    )
    (net (code "243") (name "unconnected-(U$4-PadNC)") (class "Default")
      (node (ref "U$4") (pin "NC") (pinfunction "NC_NC") (pintype "bidirectional"))
    )
  )
)
